# ESP32_Final.net
KiCad netlist of a schematic drawn in EAGLE
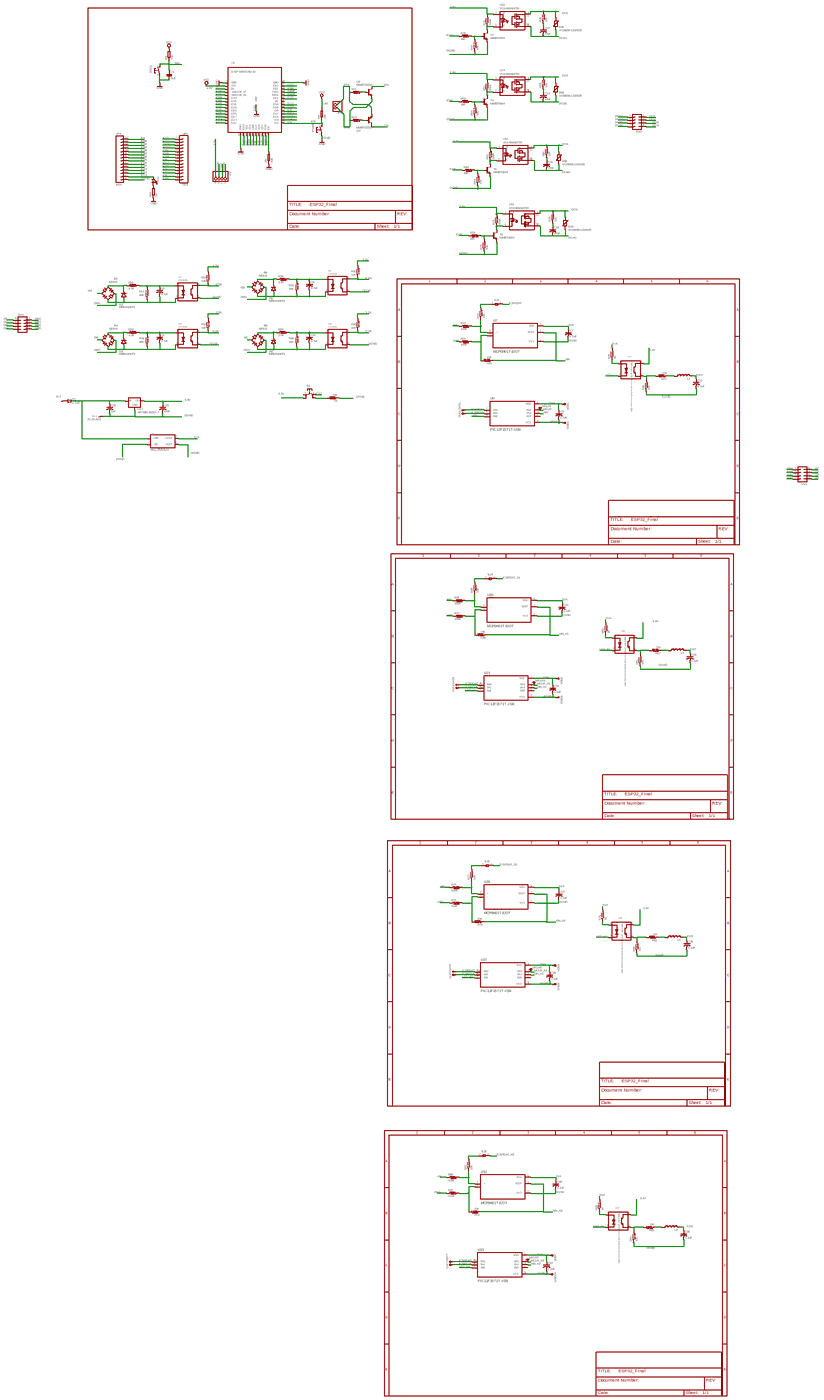
[diagram p0: schematic, sheet 1, overview]
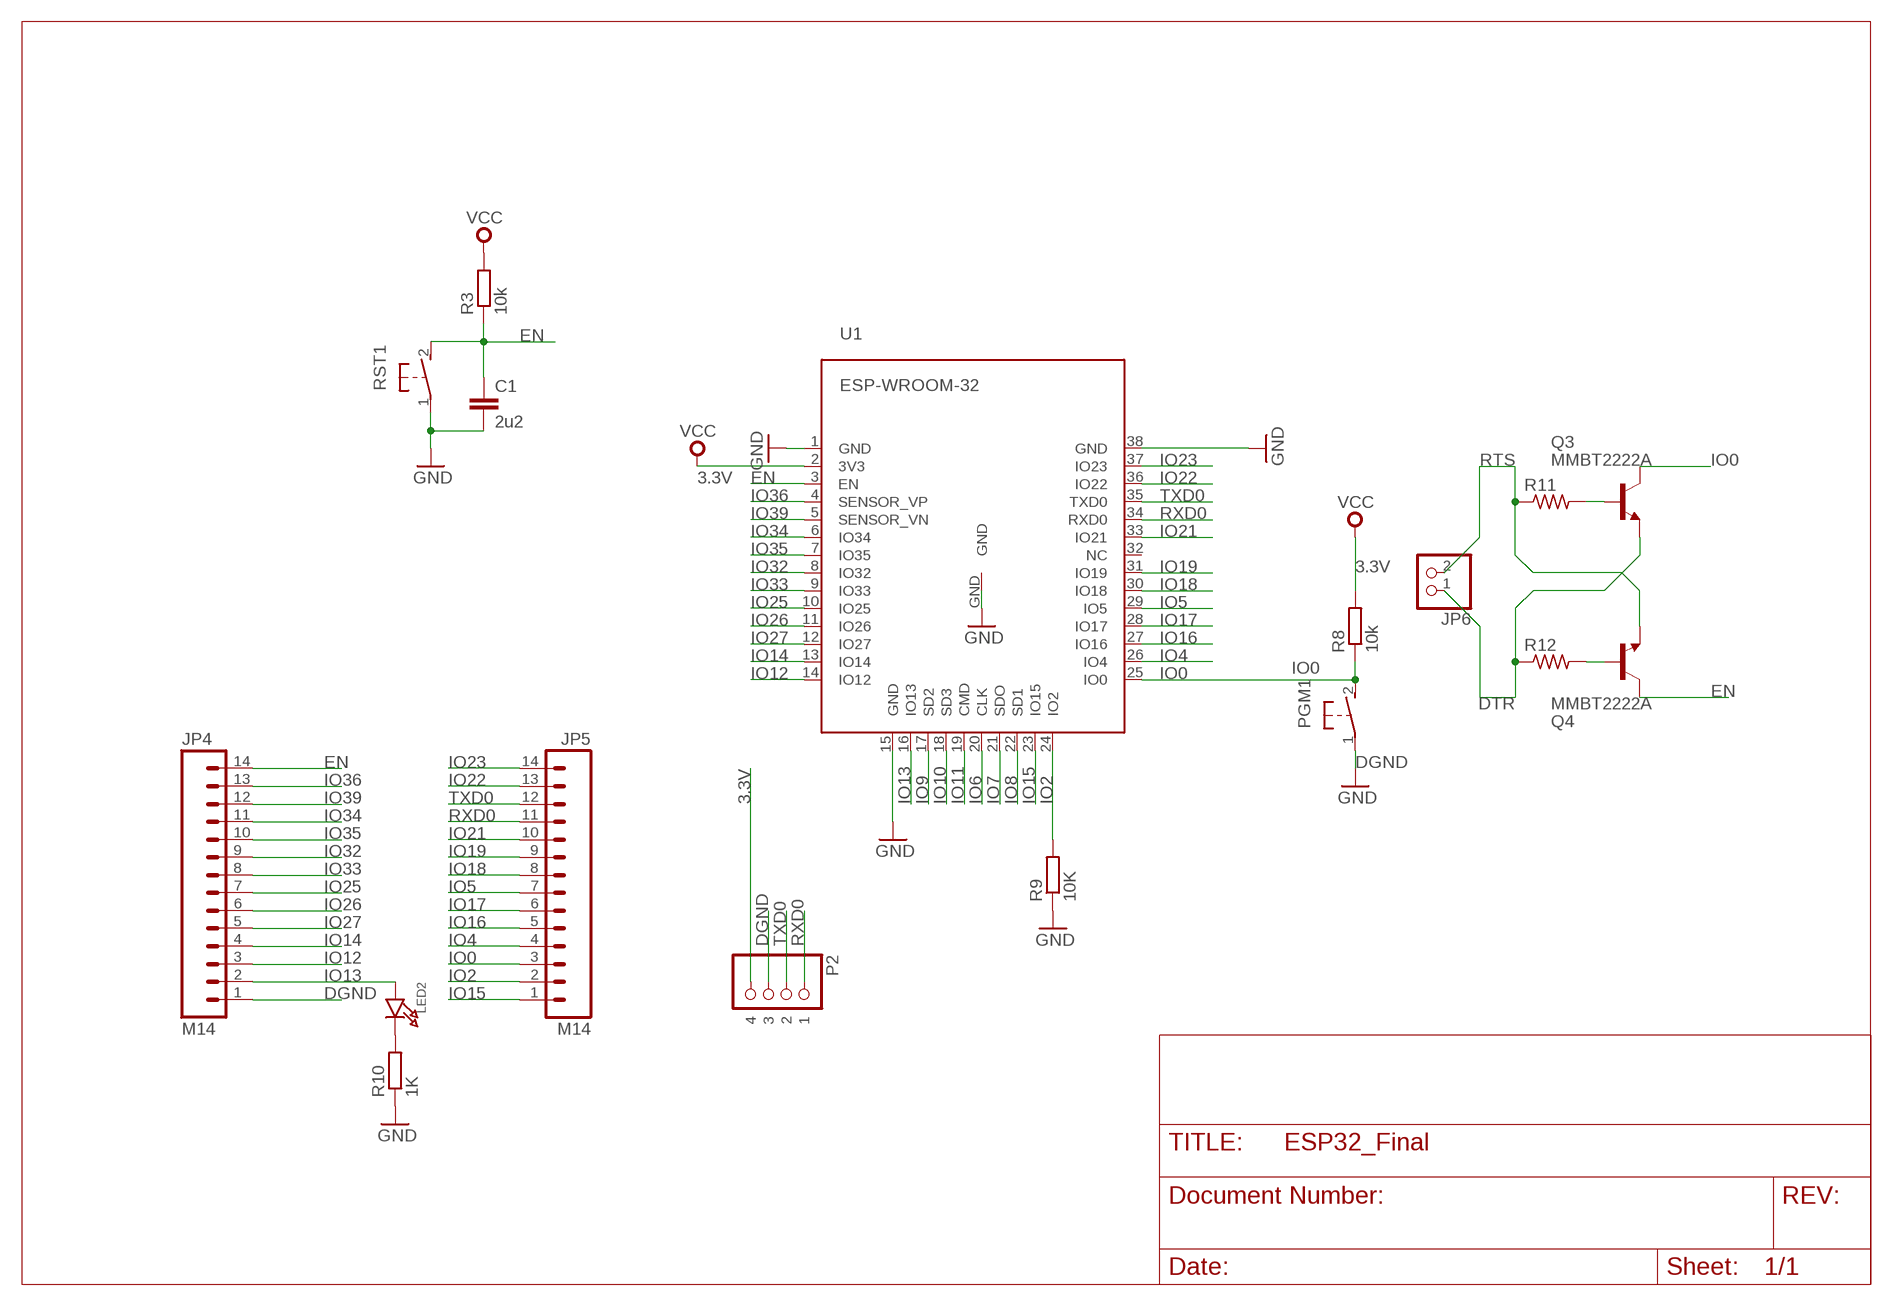
[diagram p1: schematic, sheet 1, part 1 of 5]
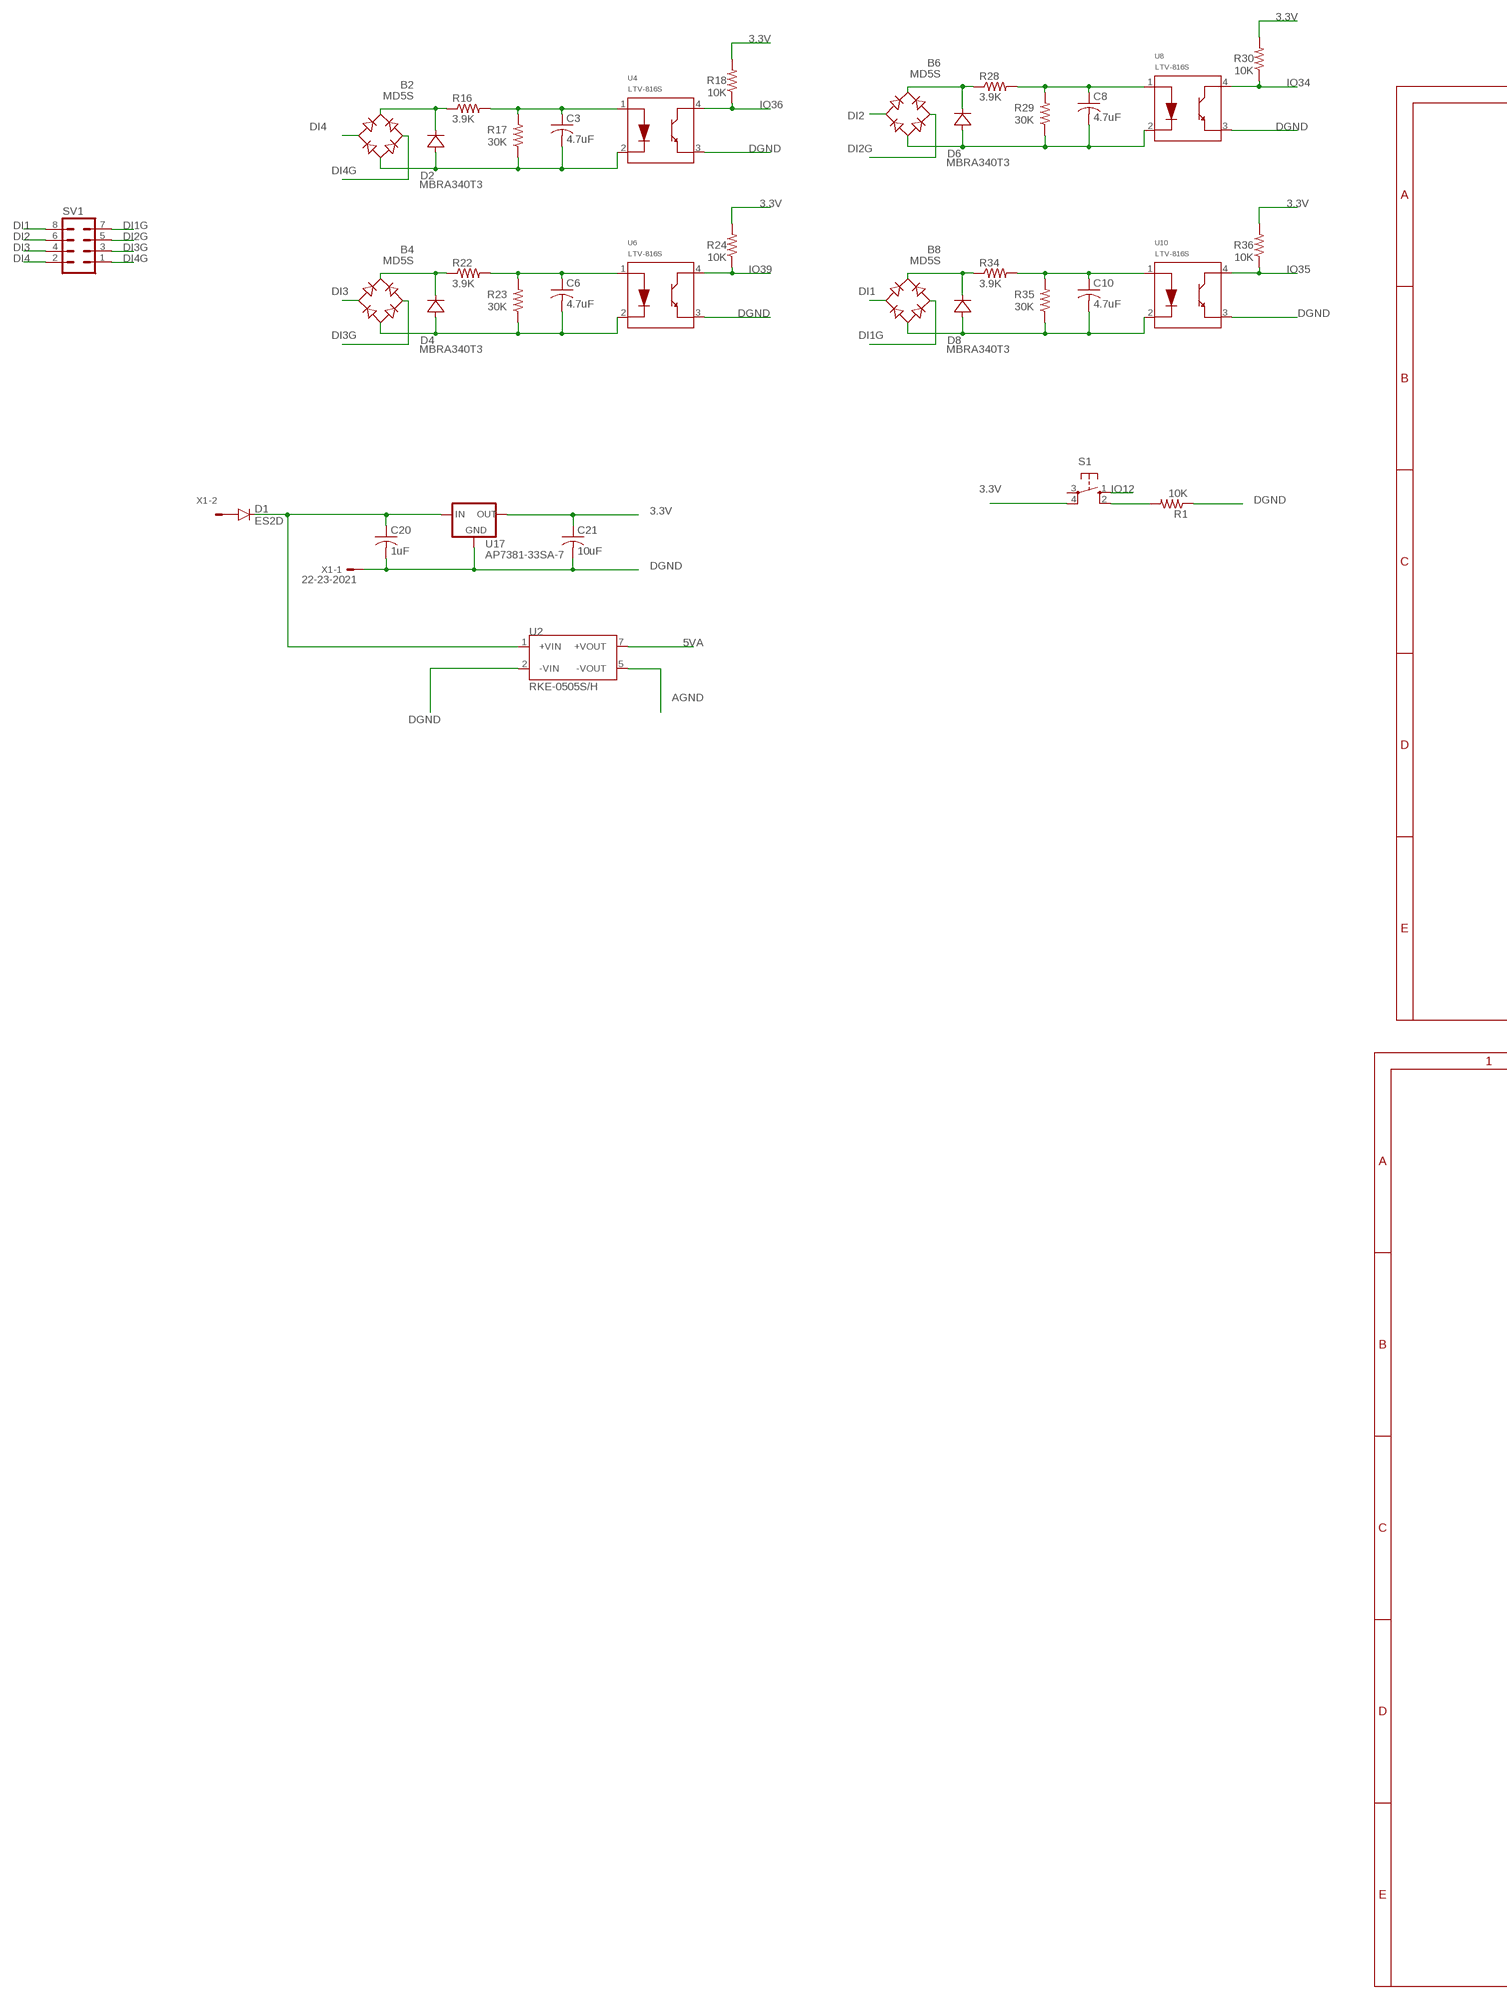
[diagram p2: schematic, sheet 1, part 2 of 5]
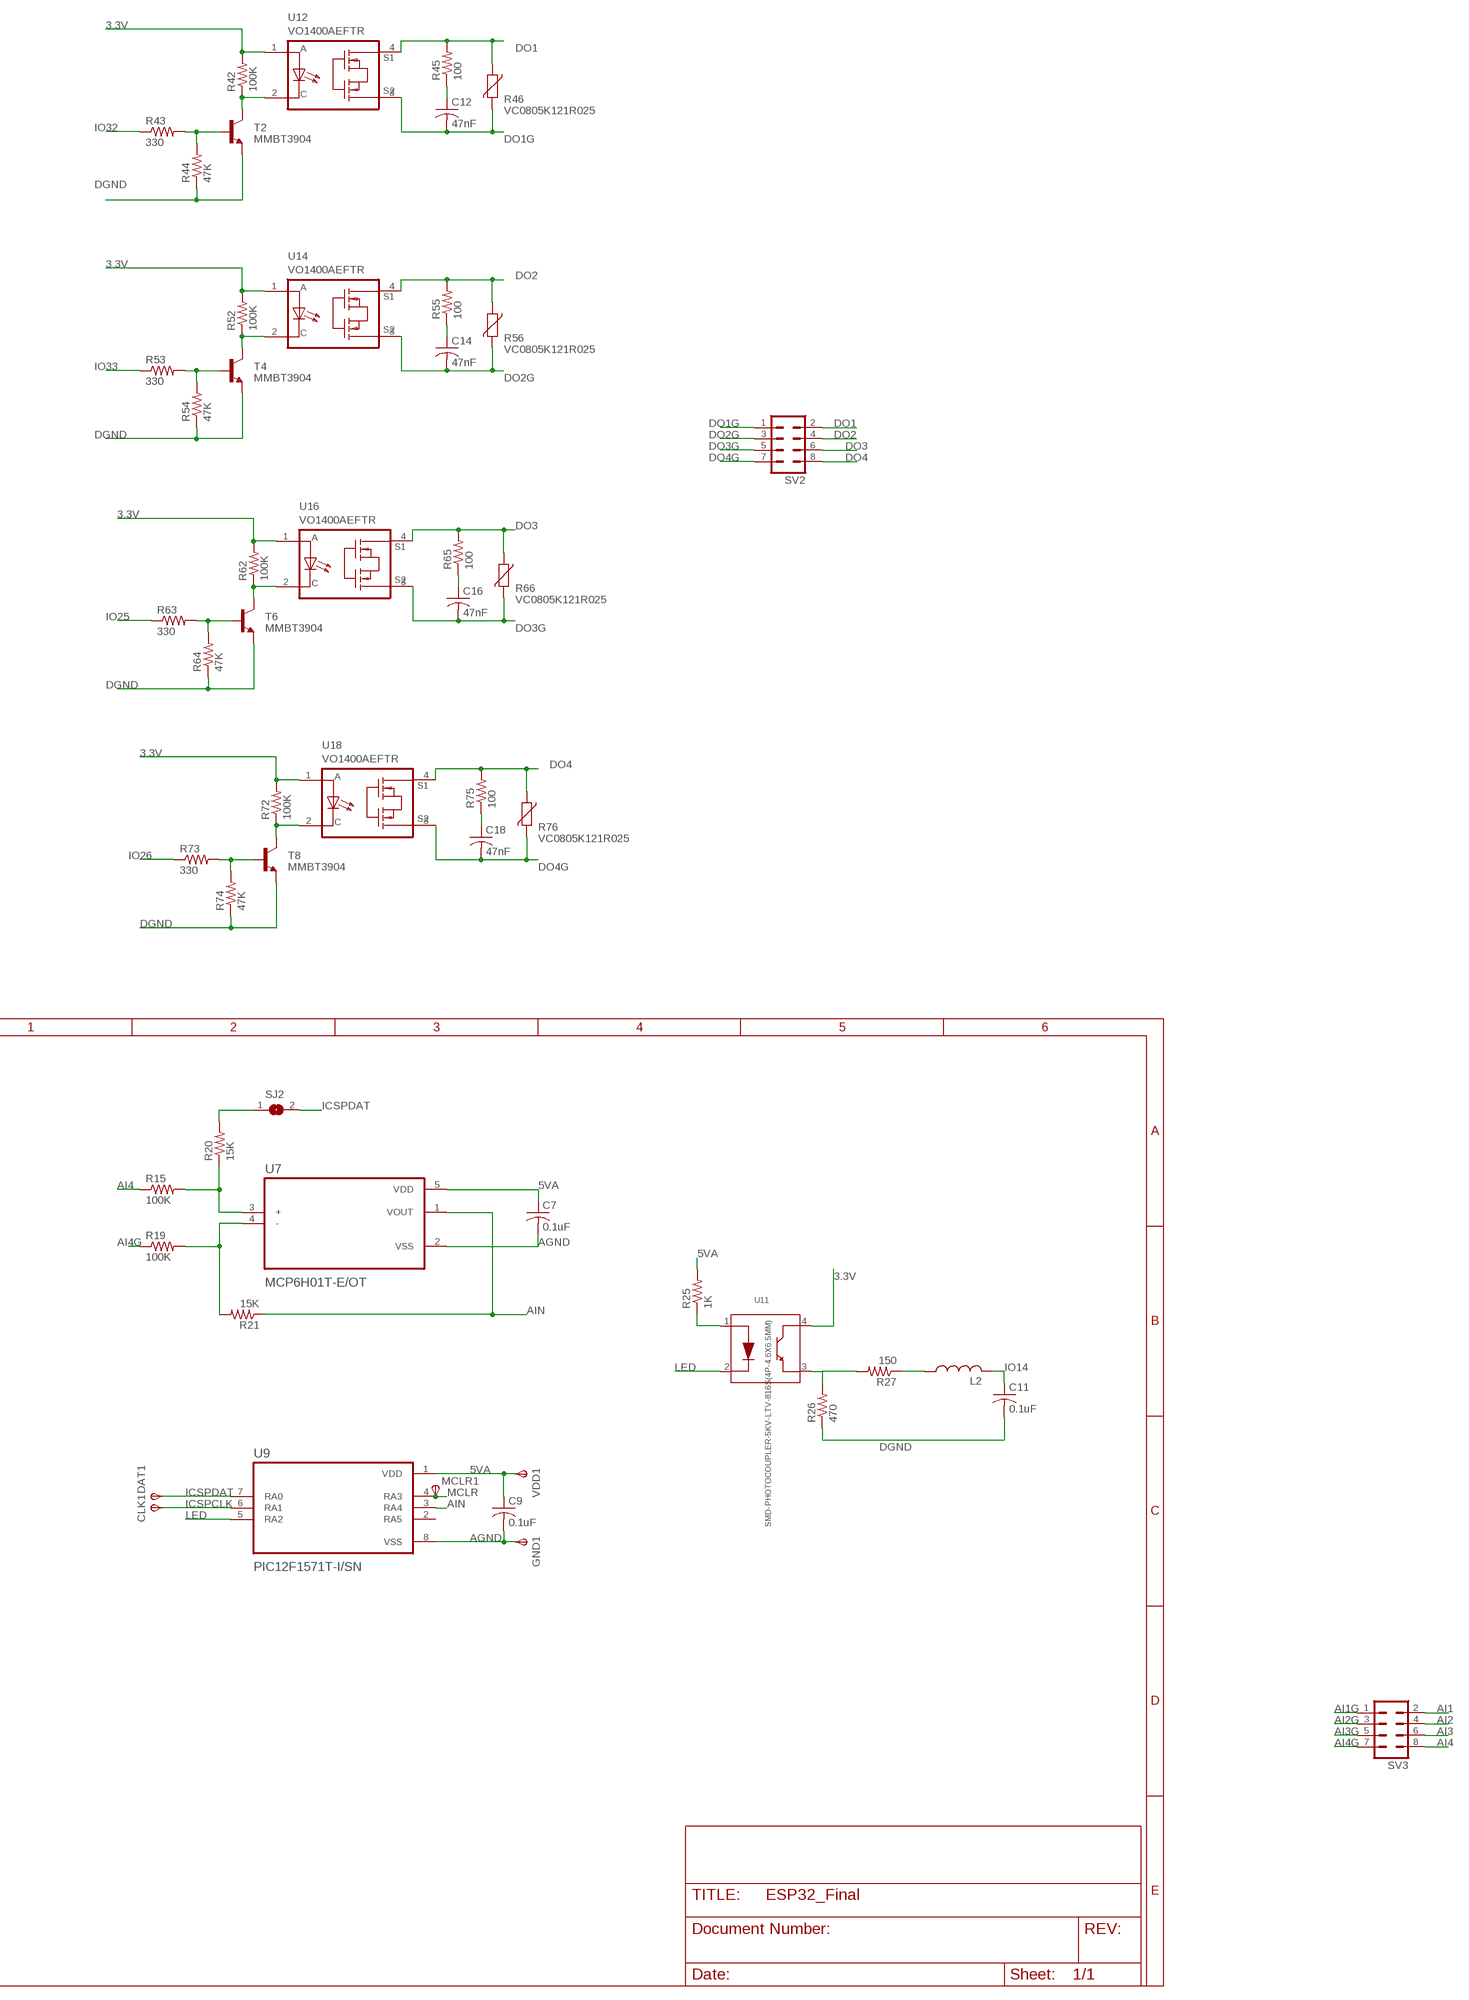
[diagram p3: schematic, sheet 1, part 3 of 5]
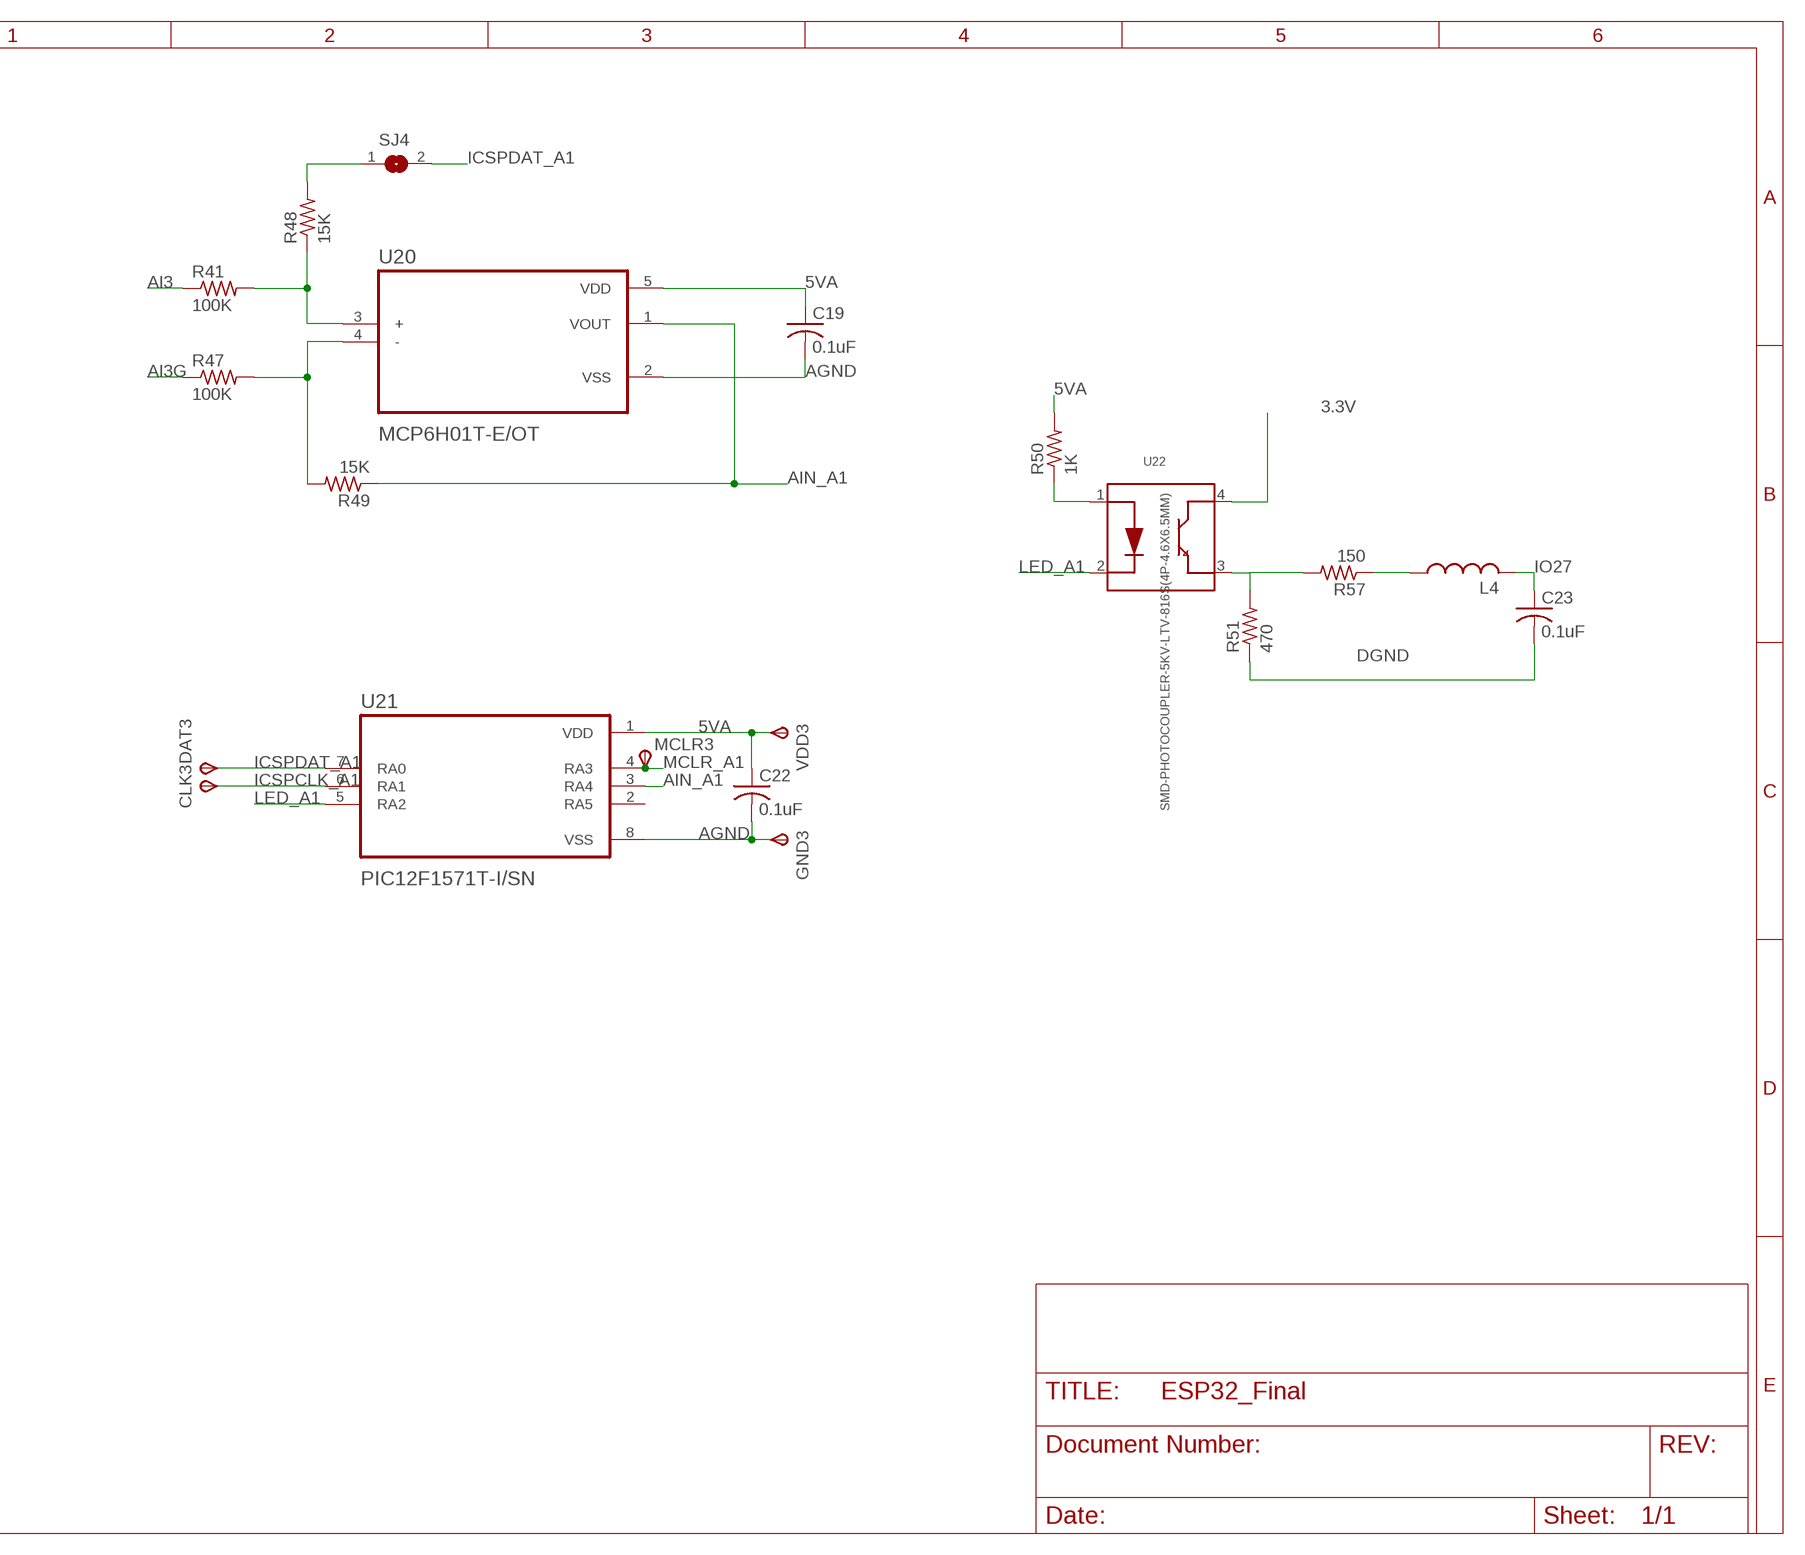
[diagram p4: schematic, sheet 1, part 4 of 5]
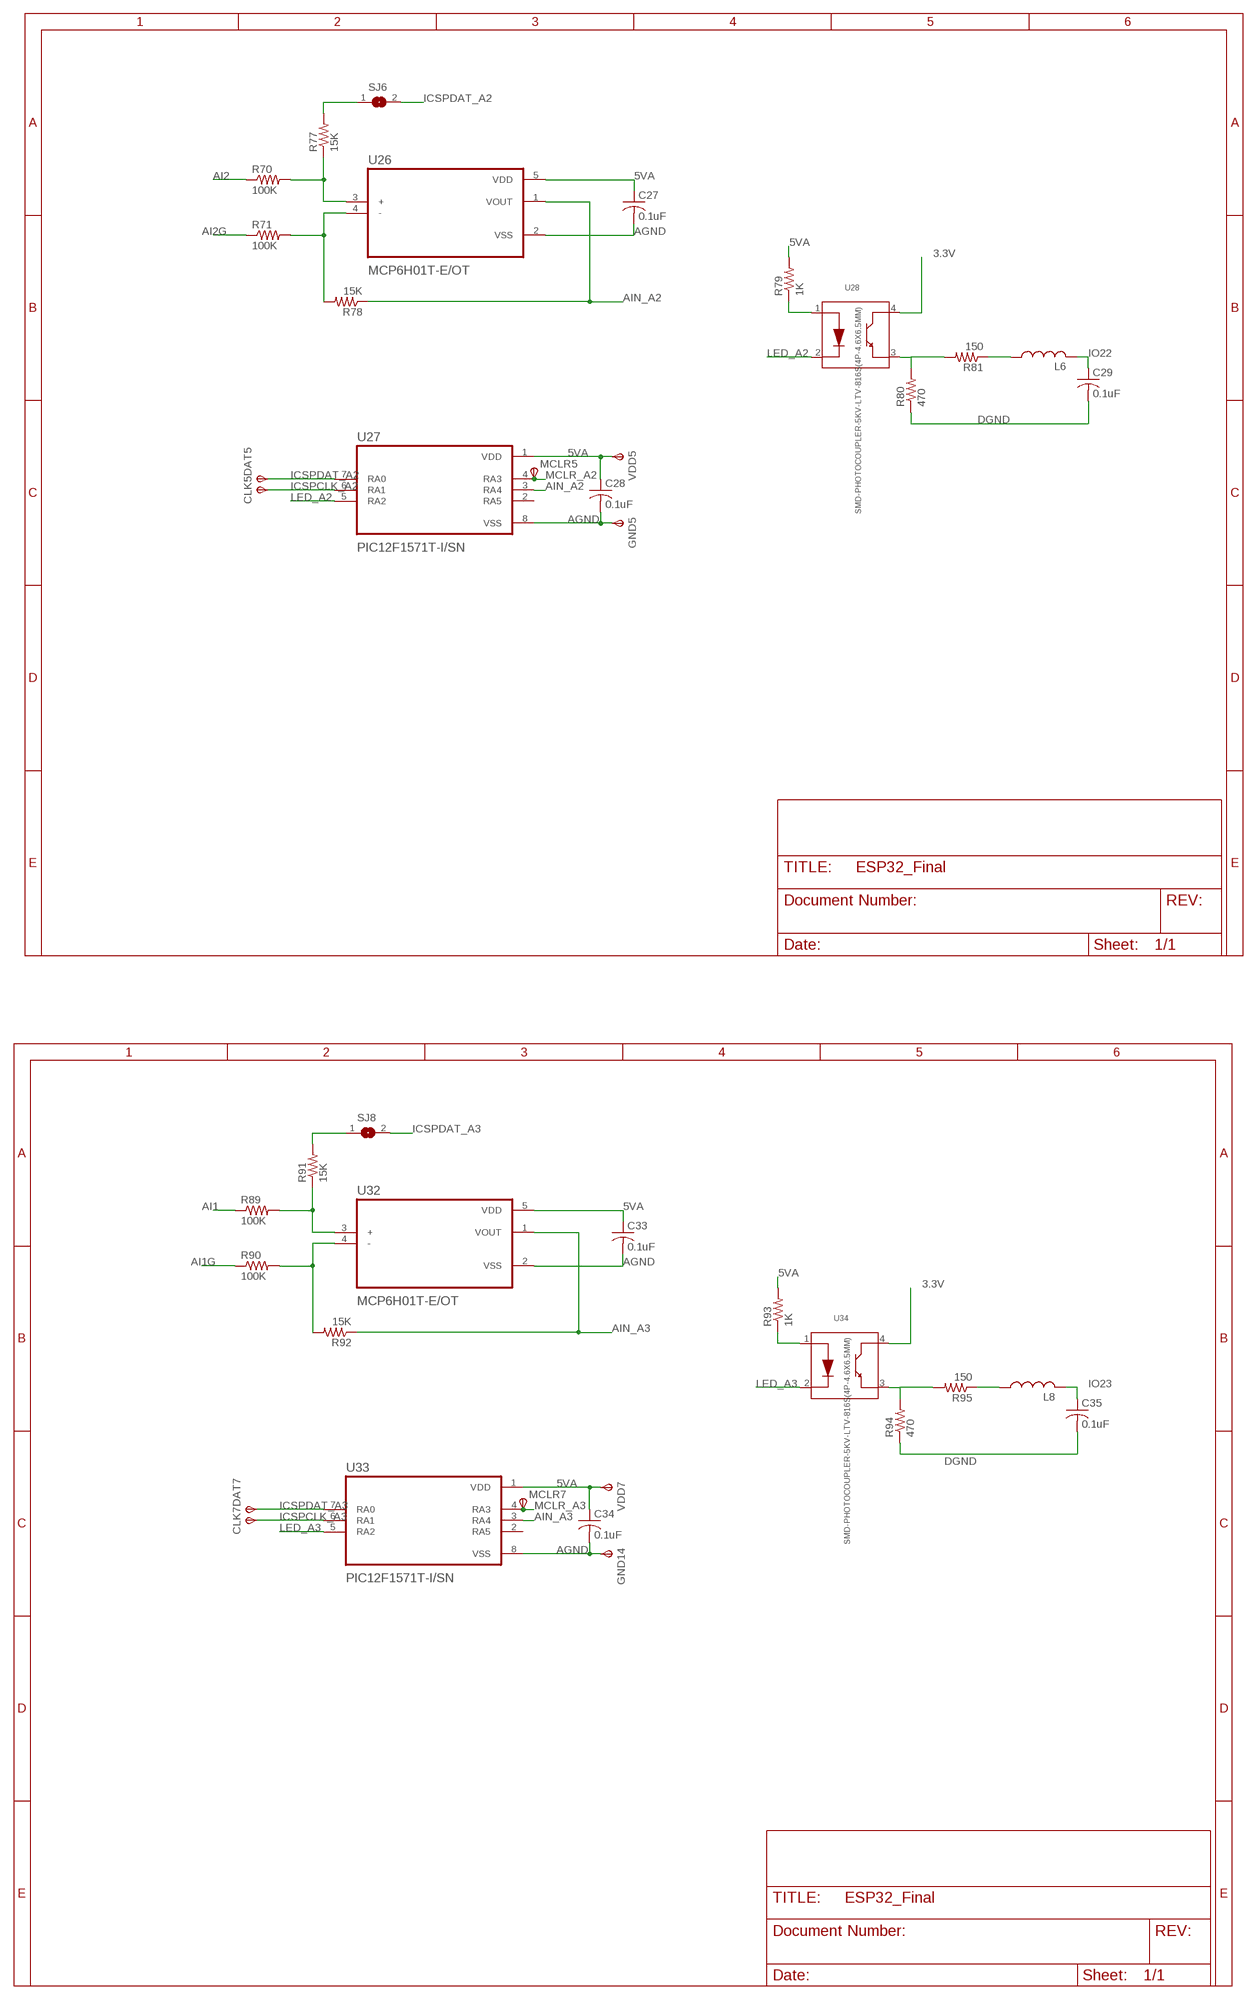
[diagram p5: schematic, sheet 1, part 5 of 5]

(export (version "E")
  (design (tool "Eeschema 10.0.6"))
  (components
    (comp (ref "B2")
      (value "MD5S")
      (footprint "eagle-import:TO-269AA")
      (libsource (lib "eagle-import") (part "RECTIFIER-S80"))
    )
    (comp (ref "B4")
      (value "MD5S")
      (footprint "eagle-import:TO-269AA")
      (libsource (lib "eagle-import") (part "RECTIFIER-S80"))
    )
    (comp (ref "B6")
      (value "MD5S")
      (footprint "eagle-import:TO-269AA")
      (libsource (lib "eagle-import") (part "RECTIFIER-S80"))
    )
    (comp (ref "B8")
      (value "MD5S")
      (footprint "eagle-import:TO-269AA")
      (libsource (lib "eagle-import") (part "RECTIFIER-S80"))
    )
    (comp (ref "C1")
      (value "2u2")
      (footprint "eagle-import:C0603")
      (libsource (lib "eagle-import") (part "C-EUC0603"))
    )
    (comp (ref "C3")
      (value "4.7uF")
      (footprint "eagle-import:C0805")
      (libsource (lib "eagle-import") (part "C-USC0805"))
    )
    (comp (ref "C6")
      (value "4.7uF")
      (footprint "eagle-import:C0805")
      (libsource (lib "eagle-import") (part "C-USC0805"))
    )
    (comp (ref "C7")
      (value "0.1uF")
      (footprint "eagle-import:C0603")
      (libsource (lib "eagle-import") (part "C-USC0603"))
    )
    (comp (ref "C8")
      (value "4.7uF")
      (footprint "eagle-import:C0805")
      (libsource (lib "eagle-import") (part "C-USC0805"))
    )
    (comp (ref "C9")
      (value "0.1uF")
      (footprint "eagle-import:C0603")
      (libsource (lib "eagle-import") (part "C-USC0603"))
    )
    (comp (ref "C10")
      (value "4.7uF")
      (footprint "eagle-import:C0805")
      (libsource (lib "eagle-import") (part "C-USC0805"))
    )
    (comp (ref "C11")
      (value "0.1uF")
      (footprint "eagle-import:C0603")
      (libsource (lib "eagle-import") (part "C-USC0603"))
    )
    (comp (ref "C12")
      (value "47nF")
      (footprint "eagle-import:C0805")
      (libsource (lib "eagle-import") (part "C-USC0805"))
    )
    (comp (ref "C14")
      (value "47nF")
      (footprint "eagle-import:C0805")
      (libsource (lib "eagle-import") (part "C-USC0805"))
    )
    (comp (ref "C16")
      (value "47nF")
      (footprint "eagle-import:C0805")
      (libsource (lib "eagle-import") (part "C-USC0805"))
    )
    (comp (ref "C18")
      (value "47nF")
      (footprint "eagle-import:C0805")
      (libsource (lib "eagle-import") (part "C-USC0805"))
    )
    (comp (ref "C19")
      (value "0.1uF")
      (footprint "eagle-import:C0603")
      (libsource (lib "eagle-import") (part "C-USC0603"))
    )
    (comp (ref "C20")
      (value "1uF")
      (footprint "eagle-import:C0603")
      (libsource (lib "eagle-import") (part "C-USC0603"))
    )
    (comp (ref "C21")
      (value "10uF")
      (footprint "eagle-import:C0603")
      (libsource (lib "eagle-import") (part "C-USC0603"))
    )
    (comp (ref "C22")
      (value "0.1uF")
      (footprint "eagle-import:C0603")
      (libsource (lib "eagle-import") (part "C-USC0603"))
    )
    (comp (ref "C23")
      (value "0.1uF")
      (footprint "eagle-import:C0603")
      (libsource (lib "eagle-import") (part "C-USC0603"))
    )
    (comp (ref "C27")
      (value "0.1uF")
      (footprint "eagle-import:C0603")
      (libsource (lib "eagle-import") (part "C-USC0603"))
    )
    (comp (ref "C28")
      (value "0.1uF")
      (footprint "eagle-import:C0603")
      (libsource (lib "eagle-import") (part "C-USC0603"))
    )
    (comp (ref "C29")
      (value "0.1uF")
      (footprint "eagle-import:C0603")
      (libsource (lib "eagle-import") (part "C-USC0603"))
    )
    (comp (ref "C33")
      (value "0.1uF")
      (footprint "eagle-import:C0603")
      (libsource (lib "eagle-import") (part "C-USC0603"))
    )
    (comp (ref "C34")
      (value "0.1uF")
      (footprint "eagle-import:C0603")
      (libsource (lib "eagle-import") (part "C-USC0603"))
    )
    (comp (ref "C35")
      (value "0.1uF")
      (footprint "eagle-import:C0603")
      (libsource (lib "eagle-import") (part "C-USC0603"))
    )
    (comp (ref "CLK1")
      (value "TPSTP14R")
      (footprint "eagle-import:TP14R")
      (libsource (lib "eagle-import") (part "TPSTP14R"))
    )
    (comp (ref "CLK3")
      (value "TPSTP14R")
      (footprint "eagle-import:TP14R")
      (libsource (lib "eagle-import") (part "TPSTP14R"))
    )
    (comp (ref "CLK5")
      (value "TPSTP14R")
      (footprint "eagle-import:TP14R")
      (libsource (lib "eagle-import") (part "TPSTP14R"))
    )
    (comp (ref "CLK7")
      (value "TPSTP14R")
      (footprint "eagle-import:TP14R")
      (libsource (lib "eagle-import") (part "TPSTP14R"))
    )
    (comp (ref "D1")
      (value "ES2D")
      (footprint "eagle-import:SMB")
      (libsource (lib "eagle-import") (part "ES2D"))
    )
    (comp (ref "D2")
      (value "MBRA340T3")
      (footprint "eagle-import:SMA")
      (libsource (lib "eagle-import") (part "MBRA340T3"))
    )
    (comp (ref "D4")
      (value "MBRA340T3")
      (footprint "eagle-import:SMA")
      (libsource (lib "eagle-import") (part "MBRA340T3"))
    )
    (comp (ref "D6")
      (value "MBRA340T3")
      (footprint "eagle-import:SMA")
      (libsource (lib "eagle-import") (part "MBRA340T3"))
    )
    (comp (ref "D8")
      (value "MBRA340T3")
      (footprint "eagle-import:SMA")
      (libsource (lib "eagle-import") (part "MBRA340T3"))
    )
    (comp (ref "DAT1")
      (value "TPSTP14R")
      (footprint "eagle-import:TP14R")
      (libsource (lib "eagle-import") (part "TPSTP14R"))
    )
    (comp (ref "DAT3")
      (value "TPSTP14R")
      (footprint "eagle-import:TP14R")
      (libsource (lib "eagle-import") (part "TPSTP14R"))
    )
    (comp (ref "DAT5")
      (value "TPSTP14R")
      (footprint "eagle-import:TP14R")
      (libsource (lib "eagle-import") (part "TPSTP14R"))
    )
    (comp (ref "DAT7")
      (value "TPSTP14R")
      (footprint "eagle-import:TP14R")
      (libsource (lib "eagle-import") (part "TPSTP14R"))
    )
    (comp (ref "GND1")
      (value "TPSTP14R")
      (footprint "eagle-import:TP14R")
      (libsource (lib "eagle-import") (part "TPSTP14R"))
    )
    (comp (ref "GND3")
      (value "TPSTP14R")
      (footprint "eagle-import:TP14R")
      (libsource (lib "eagle-import") (part "TPSTP14R"))
    )
    (comp (ref "GND5")
      (value "TPSTP14R")
      (footprint "eagle-import:TP14R")
      (libsource (lib "eagle-import") (part "TPSTP14R"))
    )
    (comp (ref "GND14")
      (value "TPSTP14R")
      (footprint "eagle-import:TP14R")
      (libsource (lib "eagle-import") (part "TPSTP14R"))
    )
    (comp (ref "JP4")
      (value "M14")
      (footprint "eagle-import:1X14")
      (libsource (lib "eagle-import") (part "M14"))
    )
    (comp (ref "JP5")
      (value "M14")
      (footprint "eagle-import:1X14")
      (libsource (lib "eagle-import") (part "M14"))
    )
    (comp (ref "JP6")
      (value "HEADER-1X2ROUND")
      (footprint "eagle-import:1X02_ROUND")
      (libsource (lib "eagle-import") (part "HEADER-1X2ROUND"))
    )
    (comp (ref "L2")
      (value "L-USL2012C")
      (footprint "eagle-import:L2012C")
      (libsource (lib "eagle-import") (part "L-USL2012C"))
    )
    (comp (ref "L4")
      (value "L-USL2012C")
      (footprint "eagle-import:L2012C")
      (libsource (lib "eagle-import") (part "L-USL2012C"))
    )
    (comp (ref "L6")
      (value "L-USL2012C")
      (footprint "eagle-import:L2012C")
      (libsource (lib "eagle-import") (part "L-USL2012C"))
    )
    (comp (ref "L8")
      (value "L-USL2012C")
      (footprint "eagle-import:L2012C")
      (libsource (lib "eagle-import") (part "L-USL2012C"))
    )
    (comp (ref "LED2")
      (value "LED0603")
      (footprint "eagle-import:CHIPLED_0603")
      (libsource (lib "eagle-import") (part "LED0603"))
    )
    (comp (ref "MCLR1")
      (value "TPSTP14R")
      (footprint "eagle-import:TP14R")
      (libsource (lib "eagle-import") (part "TPSTP14R"))
    )
    (comp (ref "MCLR3")
      (value "TPSTP14R")
      (footprint "eagle-import:TP14R")
      (libsource (lib "eagle-import") (part "TPSTP14R"))
    )
    (comp (ref "MCLR5")
      (value "TPSTP14R")
      (footprint "eagle-import:TP14R")
      (libsource (lib "eagle-import") (part "TPSTP14R"))
    )
    (comp (ref "MCLR7")
      (value "TPSTP14R")
      (footprint "eagle-import:TP14R")
      (libsource (lib "eagle-import") (part "TPSTP14R"))
    )
    (comp (ref "P2")
      (value "HEADER-1X4ROUND")
      (footprint "eagle-import:1X04_ROUND")
      (libsource (lib "eagle-import") (part "HEADER-1X4ROUND"))
    )
    (comp (ref "PGM1")
      (value "DTSM-3")
      (footprint "eagle-import:DTSM-3")
      (libsource (lib "eagle-import") (part "DTSM-3"))
    )
    (comp (ref "Q3")
      (value "MMBT2222A")
      (footprint "eagle-import:SOT23")
      (fields (field (name "MF") "STMicroelectronics"))
      (libsource (lib "eagle-import") (part "MMBT2222A"))
    )
    (comp (ref "Q4")
      (value "MMBT2222A")
      (footprint "eagle-import:SOT23")
      (fields (field (name "MF") "STMicroelectronics"))
      (libsource (lib "eagle-import") (part "MMBT2222A"))
    )
    (comp (ref "R1")
      (value "10K")
      (footprint "eagle-import:R0805")
      (libsource (lib "eagle-import") (part "rcl_334_R-US_R0805"))
    )
    (comp (ref "R3")
      (value "10k")
      (footprint "eagle-import:R0603@1")
      (libsource (lib "eagle-import") (part "R-EU_R0603"))
    )
    (comp (ref "R8")
      (value "10k")
      (footprint "eagle-import:R0603@1")
      (libsource (lib "eagle-import") (part "R-EU_R0603"))
    )
    (comp (ref "R9")
      (value "10K")
      (footprint "eagle-import:R0603@1")
      (libsource (lib "eagle-import") (part "R-EU_R0603"))
    )
    (comp (ref "R10")
      (value "1K")
      (footprint "eagle-import:R0603@1")
      (libsource (lib "eagle-import") (part "R-EU_R0603"))
    )
    (comp (ref "R11")
      (value "R-US_R0603")
      (footprint "eagle-import:R0603")
      (libsource (lib "eagle-import") (part "rcl_334_R-US_R0603"))
    )
    (comp (ref "R12")
      (value "R-US_R0603")
      (footprint "eagle-import:R0603")
      (libsource (lib "eagle-import") (part "rcl_334_R-US_R0603"))
    )
    (comp (ref "R15")
      (value "100K")
      (footprint "eagle-import:R0805")
      (libsource (lib "eagle-import") (part "rcl_334_R-US_R0805"))
    )
    (comp (ref "R16")
      (value "3.9K")
      (footprint "eagle-import:R0805")
      (libsource (lib "eagle-import") (part "rcl_334_R-US_R0805"))
    )
    (comp (ref "R17")
      (value "30K")
      (footprint "eagle-import:R0805")
      (libsource (lib "eagle-import") (part "rcl_334_R-US_R0805"))
    )
    (comp (ref "R18")
      (value "10K")
      (footprint "eagle-import:R0603")
      (libsource (lib "eagle-import") (part "R-US_R0603"))
    )
    (comp (ref "R19")
      (value "100K")
      (footprint "eagle-import:R0805")
      (libsource (lib "eagle-import") (part "rcl_334_R-US_R0805"))
    )
    (comp (ref "R20")
      (value "15K")
      (footprint "eagle-import:R0603")
      (libsource (lib "eagle-import") (part "rcl_334_R-US_R0603"))
    )
    (comp (ref "R21")
      (value "15K")
      (footprint "eagle-import:R0603")
      (libsource (lib "eagle-import") (part "rcl_334_R-US_R0603"))
    )
    (comp (ref "R22")
      (value "3.9K")
      (footprint "eagle-import:R0805")
      (libsource (lib "eagle-import") (part "rcl_334_R-US_R0805"))
    )
    (comp (ref "R23")
      (value "30K")
      (footprint "eagle-import:R0805")
      (libsource (lib "eagle-import") (part "rcl_334_R-US_R0805"))
    )
    (comp (ref "R24")
      (value "10K")
      (footprint "eagle-import:R0603")
      (libsource (lib "eagle-import") (part "R-US_R0603"))
    )
    (comp (ref "R25")
      (value "1K")
      (footprint "eagle-import:R0805")
      (libsource (lib "eagle-import") (part "rcl_334_R-US_R0805"))
    )
    (comp (ref "R26")
      (value "470")
      (footprint "eagle-import:R0805")
      (libsource (lib "eagle-import") (part "rcl_334_R-US_R0805"))
    )
    (comp (ref "R27")
      (value "150")
      (footprint "eagle-import:R0805")
      (libsource (lib "eagle-import") (part "rcl_334_R-US_R0805"))
    )
    (comp (ref "R28")
      (value "3.9K")
      (footprint "eagle-import:R0805")
      (libsource (lib "eagle-import") (part "rcl_334_R-US_R0805"))
    )
    (comp (ref "R29")
      (value "30K")
      (footprint "eagle-import:R0805")
      (libsource (lib "eagle-import") (part "rcl_334_R-US_R0805"))
    )
    (comp (ref "R30")
      (value "10K")
      (footprint "eagle-import:R0603")
      (libsource (lib "eagle-import") (part "R-US_R0603"))
    )
    (comp (ref "R34")
      (value "3.9K")
      (footprint "eagle-import:R0805")
      (libsource (lib "eagle-import") (part "rcl_334_R-US_R0805"))
    )
    (comp (ref "R35")
      (value "30K")
      (footprint "eagle-import:R0805")
      (libsource (lib "eagle-import") (part "rcl_334_R-US_R0805"))
    )
    (comp (ref "R36")
      (value "10K")
      (footprint "eagle-import:R0603")
      (libsource (lib "eagle-import") (part "R-US_R0603"))
    )
    (comp (ref "R41")
      (value "100K")
      (footprint "eagle-import:R0805")
      (libsource (lib "eagle-import") (part "rcl_334_R-US_R0805"))
    )
    (comp (ref "R42")
      (value "100K")
      (footprint "eagle-import:R0603")
      (libsource (lib "eagle-import") (part "rcl_334_R-US_R0603"))
    )
    (comp (ref "R43")
      (value "330")
      (footprint "eagle-import:R0603")
      (libsource (lib "eagle-import") (part "rcl_334_R-US_R0603"))
    )
    (comp (ref "R44")
      (value "47K")
      (footprint "eagle-import:R0603")
      (libsource (lib "eagle-import") (part "rcl_334_R-US_R0603"))
    )
    (comp (ref "R45")
      (value "100")
      (footprint "eagle-import:R1210")
      (libsource (lib "eagle-import") (part "rcl_334_R-US_R1210"))
    )
    (comp (ref "R46")
      (value "VC0805K121R025")
      (footprint "eagle-import:CT_CN0805")
      (libsource (lib "eagle-import") (part "VARISTORCN0805"))
    )
    (comp (ref "R47")
      (value "100K")
      (footprint "eagle-import:R0805")
      (libsource (lib "eagle-import") (part "rcl_334_R-US_R0805"))
    )
    (comp (ref "R48")
      (value "15K")
      (footprint "eagle-import:R0603")
      (libsource (lib "eagle-import") (part "rcl_334_R-US_R0603"))
    )
    (comp (ref "R49")
      (value "15K")
      (footprint "eagle-import:R0603")
      (libsource (lib "eagle-import") (part "rcl_334_R-US_R0603"))
    )
    (comp (ref "R50")
      (value "1K")
      (footprint "eagle-import:R0805")
      (libsource (lib "eagle-import") (part "rcl_334_R-US_R0805"))
    )
    (comp (ref "R51")
      (value "470")
      (footprint "eagle-import:R0805")
      (libsource (lib "eagle-import") (part "rcl_334_R-US_R0805"))
    )
    (comp (ref "R52")
      (value "100K")
      (footprint "eagle-import:R0603")
      (libsource (lib "eagle-import") (part "rcl_334_R-US_R0603"))
    )
    (comp (ref "R53")
      (value "330")
      (footprint "eagle-import:R0603")
      (libsource (lib "eagle-import") (part "rcl_334_R-US_R0603"))
    )
    (comp (ref "R54")
      (value "47K")
      (footprint "eagle-import:R0603")
      (libsource (lib "eagle-import") (part "rcl_334_R-US_R0603"))
    )
    (comp (ref "R55")
      (value "100")
      (footprint "eagle-import:R1210")
      (libsource (lib "eagle-import") (part "rcl_334_R-US_R1210"))
    )
    (comp (ref "R56")
      (value "VC0805K121R025")
      (footprint "eagle-import:CT_CN0805")
      (libsource (lib "eagle-import") (part "VARISTORCN0805"))
    )
    (comp (ref "R57")
      (value "150")
      (footprint "eagle-import:R0805")
      (libsource (lib "eagle-import") (part "rcl_334_R-US_R0805"))
    )
    (comp (ref "R62")
      (value "100K")
      (footprint "eagle-import:R0603")
      (libsource (lib "eagle-import") (part "rcl_334_R-US_R0603"))
    )
    (comp (ref "R63")
      (value "330")
      (footprint "eagle-import:R0603")
      (libsource (lib "eagle-import") (part "rcl_334_R-US_R0603"))
    )
    (comp (ref "R64")
      (value "47K")
      (footprint "eagle-import:R0603")
      (libsource (lib "eagle-import") (part "rcl_334_R-US_R0603"))
    )
    (comp (ref "R65")
      (value "100")
      (footprint "eagle-import:R1210")
      (libsource (lib "eagle-import") (part "rcl_334_R-US_R1210"))
    )
    (comp (ref "R66")
      (value "VC0805K121R025")
      (footprint "eagle-import:CT_CN0805")
      (libsource (lib "eagle-import") (part "VARISTORCN0805"))
    )
    (comp (ref "R70")
      (value "100K")
      (footprint "eagle-import:R0805")
      (libsource (lib "eagle-import") (part "rcl_334_R-US_R0805"))
    )
    (comp (ref "R71")
      (value "100K")
      (footprint "eagle-import:R0805")
      (libsource (lib "eagle-import") (part "rcl_334_R-US_R0805"))
    )
    (comp (ref "R72")
      (value "100K")
      (footprint "eagle-import:R0603")
      (libsource (lib "eagle-import") (part "rcl_334_R-US_R0603"))
    )
    (comp (ref "R73")
      (value "330")
      (footprint "eagle-import:R0603")
      (libsource (lib "eagle-import") (part "rcl_334_R-US_R0603"))
    )
    (comp (ref "R74")
      (value "47K")
      (footprint "eagle-import:R0603")
      (libsource (lib "eagle-import") (part "rcl_334_R-US_R0603"))
    )
    (comp (ref "R75")
      (value "100")
      (footprint "eagle-import:R1210")
      (libsource (lib "eagle-import") (part "rcl_334_R-US_R1210"))
    )
    (comp (ref "R76")
      (value "VC0805K121R025")
      (footprint "eagle-import:CT_CN0805")
      (libsource (lib "eagle-import") (part "VARISTORCN0805"))
    )
    (comp (ref "R77")
      (value "15K")
      (footprint "eagle-import:R0603")
      (libsource (lib "eagle-import") (part "rcl_334_R-US_R0603"))
    )
    (comp (ref "R78")
      (value "15K")
      (footprint "eagle-import:R0603")
      (libsource (lib "eagle-import") (part "rcl_334_R-US_R0603"))
    )
    (comp (ref "R79")
      (value "1K")
      (footprint "eagle-import:R0805")
      (libsource (lib "eagle-import") (part "rcl_334_R-US_R0805"))
    )
    (comp (ref "R80")
      (value "470")
      (footprint "eagle-import:R0805")
      (libsource (lib "eagle-import") (part "rcl_334_R-US_R0805"))
    )
    (comp (ref "R81")
      (value "150")
      (footprint "eagle-import:R0805")
      (libsource (lib "eagle-import") (part "rcl_334_R-US_R0805"))
    )
    (comp (ref "R89")
      (value "100K")
      (footprint "eagle-import:R0805")
      (libsource (lib "eagle-import") (part "rcl_334_R-US_R0805"))
    )
    (comp (ref "R90")
      (value "100K")
      (footprint "eagle-import:R0805")
      (libsource (lib "eagle-import") (part "rcl_334_R-US_R0805"))
    )
    (comp (ref "R91")
      (value "15K")
      (footprint "eagle-import:R0603")
      (libsource (lib "eagle-import") (part "rcl_334_R-US_R0603"))
    )
    (comp (ref "R92")
      (value "15K")
      (footprint "eagle-import:R0603")
      (libsource (lib "eagle-import") (part "rcl_334_R-US_R0603"))
    )
    (comp (ref "R93")
      (value "1K")
      (footprint "eagle-import:R0805")
      (libsource (lib "eagle-import") (part "rcl_334_R-US_R0805"))
    )
    (comp (ref "R94")
      (value "470")
      (footprint "eagle-import:R0805")
      (libsource (lib "eagle-import") (part "rcl_334_R-US_R0805"))
    )
    (comp (ref "R95")
      (value "150")
      (footprint "eagle-import:R0805")
      (libsource (lib "eagle-import") (part "rcl_334_R-US_R0805"))
    )
    (comp (ref "RST1")
      (value "DTSM-3")
      (footprint "eagle-import:DTSM-3")
      (libsource (lib "eagle-import") (part "DTSM-3"))
    )
    (comp (ref "S1")
      (value "10-XX")
      (footprint "eagle-import:B3F-10XX")
      (fields (field (name "MPN") "B3F-1000"))
      (libsource (lib "eagle-import") (part "10-XX"))
    )
    (comp (ref "SJ2") (value "SJ") (footprint "eagle-import:SJ") (libsource (lib "eagle-import") (part "SJ")))
    (comp (ref "SJ4") (value "SJ") (footprint "eagle-import:SJ") (libsource (lib "eagle-import") (part "SJ")))
    (comp (ref "SJ6") (value "SJ") (footprint "eagle-import:SJ") (libsource (lib "eagle-import") (part "SJ")))
    (comp (ref "SJ8") (value "SJ") (footprint "eagle-import:SJ") (libsource (lib "eagle-import") (part "SJ")))
    (comp (ref "SV1")
      (value "MA04-2")
      (footprint "eagle-import:MA04-2")
      (libsource (lib "eagle-import") (part "MA04-2"))
    )
    (comp (ref "SV2")
      (value "MA04-2")
      (footprint "eagle-import:MA04-2")
      (libsource (lib "eagle-import") (part "MA04-2"))
    )
    (comp (ref "SV3")
      (value "MA04-2")
      (footprint "eagle-import:MA04-2")
      (libsource (lib "eagle-import") (part "MA04-2"))
    )
    (comp (ref "T2")
      (value "MMBT3904")
      (footprint "eagle-import:SOT23-BEC")
      (libsource (lib "eagle-import") (part "-NPN-SOT23-BECMMBT3904LT1"))
    )
    (comp (ref "T4")
      (value "MMBT3904")
      (footprint "eagle-import:SOT23-BEC")
      (libsource (lib "eagle-import") (part "-NPN-SOT23-BECMMBT3904LT1"))
    )
    (comp (ref "T6")
      (value "MMBT3904")
      (footprint "eagle-import:SOT23-BEC")
      (libsource (lib "eagle-import") (part "-NPN-SOT23-BECMMBT3904LT1"))
    )
    (comp (ref "T8")
      (value "MMBT3904")
      (footprint "eagle-import:SOT23-BEC")
      (libsource (lib "eagle-import") (part "-NPN-SOT23-BECMMBT3904LT1"))
    )
    (comp (ref "U1")
      (value "ESP-WROOM-32")
      (footprint "eagle-import:ESP-WROOM-32")
      (libsource (lib "eagle-import") (part "ESP-WROOM-32"))
    )
    (comp (ref "U2")
      (value "RKE-0505S/H")
      (footprint "eagle-import:CONV_RKE-0505S_H")
      (fields (field (name "MF") "Recom Power"))
      (libsource (lib "eagle-import") (part "RKE-0505S/H"))
    )
    (comp (ref "U4")
      (value "LTV-816S")
      (footprint "eagle-import:SMD4-2.54-4.6X6.5MM")
      (fields (field (name "MF") "Lite-On Inc."))
      (libsource (lib "eagle-import") (part "SMD-PHOTOCOUPLER-5KV-LTV-816S(4P-4.6X6.5MM)"))
    )
    (comp (ref "U6")
      (value "LTV-816S")
      (footprint "eagle-import:SMD4-2.54-4.6X6.5MM")
      (fields (field (name "MF") "Lite-On Inc."))
      (libsource (lib "eagle-import") (part "SMD-PHOTOCOUPLER-5KV-LTV-816S(4P-4.6X6.5MM)"))
    )
    (comp (ref "U7")
      (value "MCP6H01T-E/OT")
      (footprint "eagle-import:SOT95P280X145-5N")
      (fields (field (name "MF") "Microchip"))
      (libsource (lib "eagle-import") (part "MCP6H01T-E/OT"))
    )
    (comp (ref "U8")
      (value "LTV-816S")
      (footprint "eagle-import:SMD4-2.54-4.6X6.5MM")
      (fields (field (name "MF") "Lite-On Inc."))
      (libsource (lib "eagle-import") (part "SMD-PHOTOCOUPLER-5KV-LTV-816S(4P-4.6X6.5MM)"))
    )
    (comp (ref "U9")
      (value "PIC12F1571T-I/SN")
      (footprint "eagle-import:SOIC127P600X175-8N")
      (fields (field (name "MF") "Microchip"))
      (libsource (lib "eagle-import") (part "PIC12F1571T-I/SN"))
    )
    (comp (ref "U10")
      (value "LTV-816S")
      (footprint "eagle-import:SMD4-2.54-4.6X6.5MM")
      (fields (field (name "MF") "Lite-On Inc."))
      (libsource (lib "eagle-import") (part "SMD-PHOTOCOUPLER-5KV-LTV-816S(4P-4.6X6.5MM)"))
    )
    (comp (ref "U11")
      (value "SMD-PHOTOCOUPLER-5KV-LTV-816S(4P-4.6X6.5MM)")
      (footprint "eagle-import:SMD4-2.54-4.6X6.5MM")
      (fields (field (name "MF") "Lite-On Inc.") (field (name "MP") "LTV-816S"))
      (libsource (lib "eagle-import") (part "SMD-PHOTOCOUPLER-5KV-LTV-816S(4P-4.6X6.5MM)"))
    )
    (comp (ref "U12")
      (value "VO1400AEFTR")
      (footprint "eagle-import:SOIC254P695X242-4N")
      (fields (field (name "MF") "Vishay"))
      (libsource (lib "eagle-import") (part "VO1400AEFTR"))
    )
    (comp (ref "U14")
      (value "VO1400AEFTR")
      (footprint "eagle-import:SOIC254P695X242-4N")
      (fields (field (name "MF") "Vishay"))
      (libsource (lib "eagle-import") (part "VO1400AEFTR"))
    )
    (comp (ref "U16")
      (value "VO1400AEFTR")
      (footprint "eagle-import:SOIC254P695X242-4N")
      (fields (field (name "MF") "Vishay"))
      (libsource (lib "eagle-import") (part "VO1400AEFTR"))
    )
    (comp (ref "U17")
      (value "AP7381-33SA-7")
      (footprint "eagle-import:SOT23")
      (libsource (lib "eagle-import") (part "AP7381-33SA-7"))
    )
    (comp (ref "U18")
      (value "VO1400AEFTR")
      (footprint "eagle-import:SOIC254P695X242-4N")
      (fields (field (name "MF") "Vishay"))
      (libsource (lib "eagle-import") (part "VO1400AEFTR"))
    )
    (comp (ref "U20")
      (value "MCP6H01T-E/OT")
      (footprint "eagle-import:SOT95P280X145-5N")
      (fields (field (name "MF") "Microchip"))
      (libsource (lib "eagle-import") (part "MCP6H01T-E/OT"))
    )
    (comp (ref "U21")
      (value "PIC12F1571T-I/SN")
      (footprint "eagle-import:SOIC127P600X175-8N")
      (fields (field (name "MF") "Microchip"))
      (libsource (lib "eagle-import") (part "PIC12F1571T-I/SN"))
    )
    (comp (ref "U22")
      (value "SMD-PHOTOCOUPLER-5KV-LTV-816S(4P-4.6X6.5MM)")
      (footprint "eagle-import:SMD4-2.54-4.6X6.5MM")
      (fields (field (name "MF") "Lite-On Inc.") (field (name "MP") "LTV-816S"))
      (libsource (lib "eagle-import") (part "SMD-PHOTOCOUPLER-5KV-LTV-816S(4P-4.6X6.5MM)"))
    )
    (comp (ref "U26")
      (value "MCP6H01T-E/OT")
      (footprint "eagle-import:SOT95P280X145-5N")
      (fields (field (name "MF") "Microchip"))
      (libsource (lib "eagle-import") (part "MCP6H01T-E/OT"))
    )
    (comp (ref "U27")
      (value "PIC12F1571T-I/SN")
      (footprint "eagle-import:SOIC127P600X175-8N")
      (fields (field (name "MF") "Microchip"))
      (libsource (lib "eagle-import") (part "PIC12F1571T-I/SN"))
    )
    (comp (ref "U28")
      (value "SMD-PHOTOCOUPLER-5KV-LTV-816S(4P-4.6X6.5MM)")
      (footprint "eagle-import:SMD4-2.54-4.6X6.5MM")
      (fields (field (name "MF") "Lite-On Inc.") (field (name "MP") "LTV-816S"))
      (libsource (lib "eagle-import") (part "SMD-PHOTOCOUPLER-5KV-LTV-816S(4P-4.6X6.5MM)"))
    )
    (comp (ref "U32")
      (value "MCP6H01T-E/OT")
      (footprint "eagle-import:SOT95P280X145-5N")
      (fields (field (name "MF") "Microchip"))
      (libsource (lib "eagle-import") (part "MCP6H01T-E/OT"))
    )
    (comp (ref "U33")
      (value "PIC12F1571T-I/SN")
      (footprint "eagle-import:SOIC127P600X175-8N")
      (fields (field (name "MF") "Microchip"))
      (libsource (lib "eagle-import") (part "PIC12F1571T-I/SN"))
    )
    (comp (ref "U34")
      (value "SMD-PHOTOCOUPLER-5KV-LTV-816S(4P-4.6X6.5MM)")
      (footprint "eagle-import:SMD4-2.54-4.6X6.5MM")
      (fields (field (name "MF") "Lite-On Inc.") (field (name "MP") "LTV-816S"))
      (libsource (lib "eagle-import") (part "SMD-PHOTOCOUPLER-5KV-LTV-816S(4P-4.6X6.5MM)"))
    )
    (comp (ref "VDD1")
      (value "TPSTP14R")
      (footprint "eagle-import:TP14R")
      (libsource (lib "eagle-import") (part "TPSTP14R"))
    )
    (comp (ref "VDD3")
      (value "TPSTP14R")
      (footprint "eagle-import:TP14R")
      (libsource (lib "eagle-import") (part "TPSTP14R"))
    )
    (comp (ref "VDD5")
      (value "TPSTP14R")
      (footprint "eagle-import:TP14R")
      (libsource (lib "eagle-import") (part "TPSTP14R"))
    )
    (comp (ref "VDD7")
      (value "TPSTP14R")
      (footprint "eagle-import:TP14R")
      (libsource (lib "eagle-import") (part "TPSTP14R"))
    )
    (comp (ref "X1")
      (value "22-23-2021")
      (footprint "eagle-import:22-23-2021")
      (fields (field (name "MF") "MOLEX"))
      (libsource (lib "eagle-import") (part "22-23-2021"))
    )
  )
  (nets
    (net (code "1") (name "/5VA") (class "Default")
      (node (ref "C19") (pin "1") (pinfunction "1_1") (pintype "passive"))
      (node (ref "C22") (pin "1") (pinfunction "1_1") (pintype "passive"))
      (node (ref "C27") (pin "1") (pinfunction "1_1") (pintype "passive"))
      (node (ref "C28") (pin "1") (pinfunction "1_1") (pintype "passive"))
      (node (ref "C33") (pin "1") (pinfunction "1_1") (pintype "passive"))
      (node (ref "C34") (pin "1") (pinfunction "1_1") (pintype "passive"))
      (node (ref "C7") (pin "1") (pinfunction "1_1") (pintype "passive"))
      (node (ref "C9") (pin "1") (pinfunction "1_1") (pintype "passive"))
      (node (ref "R25") (pin "2") (pinfunction "2_2") (pintype "passive"))
      (node (ref "R50") (pin "2") (pinfunction "2_2") (pintype "passive"))
      (node (ref "R79") (pin "2") (pinfunction "2_2") (pintype "passive"))
      (node (ref "R93") (pin "2") (pinfunction "2_2") (pintype "passive"))
      (node (ref "U2") (pin "7") (pinfunction "+VOUT_7") (pintype "output"))
      (node (ref "U20") (pin "5") (pinfunction "VDD_5") (pintype "power_in"))
      (node (ref "U21") (pin "1") (pinfunction "VDD_1") (pintype "power_in"))
      (node (ref "U26") (pin "5") (pinfunction "VDD_5") (pintype "power_in"))
      (node (ref "U27") (pin "1") (pinfunction "VDD_1") (pintype "power_in"))
      (node (ref "U32") (pin "5") (pinfunction "VDD_5") (pintype "power_in"))
      (node (ref "U33") (pin "1") (pinfunction "VDD_1") (pintype "power_in"))
      (node (ref "U7") (pin "5") (pinfunction "VDD_5") (pintype "power_in"))
      (node (ref "U9") (pin "1") (pinfunction "VDD_1") (pintype "power_in"))
      (node (ref "VDD1") (pin "TP") (pinfunction "PP_TP") (pintype "input"))
      (node (ref "VDD3") (pin "TP") (pinfunction "PP_TP") (pintype "input"))
      (node (ref "VDD5") (pin "TP") (pinfunction "PP_TP") (pintype "input"))
      (node (ref "VDD7") (pin "TP") (pinfunction "PP_TP") (pintype "input"))
    )
    (net (code "2") (name "/AGND") (class "Default")
      (node (ref "C19") (pin "2") (pinfunction "2_2") (pintype "passive"))
      (node (ref "C22") (pin "2") (pinfunction "2_2") (pintype "passive"))
      (node (ref "C27") (pin "2") (pinfunction "2_2") (pintype "passive"))
      (node (ref "C28") (pin "2") (pinfunction "2_2") (pintype "passive"))
      (node (ref "C33") (pin "2") (pinfunction "2_2") (pintype "passive"))
      (node (ref "C34") (pin "2") (pinfunction "2_2") (pintype "passive"))
      (node (ref "C7") (pin "2") (pinfunction "2_2") (pintype "passive"))
      (node (ref "C9") (pin "2") (pinfunction "2_2") (pintype "passive"))
      (node (ref "GND1") (pin "TP") (pinfunction "PP_TP") (pintype "input"))
      (node (ref "GND14") (pin "TP") (pinfunction "PP_TP") (pintype "input"))
      (node (ref "GND3") (pin "TP") (pinfunction "PP_TP") (pintype "input"))
      (node (ref "GND5") (pin "TP") (pinfunction "PP_TP") (pintype "input"))
      (node (ref "U2") (pin "5") (pinfunction "-VOUT_5") (pintype "output"))
      (node (ref "U20") (pin "2") (pinfunction "VSS_2") (pintype "power_in"))
      (node (ref "U21") (pin "8") (pinfunction "VSS_8") (pintype "power_in"))
      (node (ref "U26") (pin "2") (pinfunction "VSS_2") (pintype "power_in"))
      (node (ref "U27") (pin "8") (pinfunction "VSS_8") (pintype "power_in"))
      (node (ref "U32") (pin "2") (pinfunction "VSS_2") (pintype "power_in"))
      (node (ref "U33") (pin "8") (pinfunction "VSS_8") (pintype "power_in"))
      (node (ref "U7") (pin "2") (pinfunction "VSS_2") (pintype "power_in"))
      (node (ref "U9") (pin "8") (pinfunction "VSS_8") (pintype "power_in"))
    )
    (net (code "3") (name "/AI1") (class "Default")
      (node (ref "R89") (pin "1") (pinfunction "1_1") (pintype "passive"))
      (node (ref "SV3") (pin "2") (pinfunction "2_2") (pintype "passive"))
    )
    (net (code "4") (name "/AI1G") (class "Default")
      (node (ref "R90") (pin "1") (pinfunction "1_1") (pintype "passive"))
      (node (ref "SV3") (pin "1") (pinfunction "1_1") (pintype "passive"))
    )
    (net (code "5") (name "/AI2") (class "Default")
      (node (ref "R70") (pin "1") (pinfunction "1_1") (pintype "passive"))
      (node (ref "SV3") (pin "4") (pinfunction "4_4") (pintype "passive"))
    )
    (net (code "6") (name "/AI2G") (class "Default")
      (node (ref "R71") (pin "1") (pinfunction "1_1") (pintype "passive"))
      (node (ref "SV3") (pin "3") (pinfunction "3_3") (pintype "passive"))
    )
    (net (code "7") (name "/AI3") (class "Default")
      (node (ref "R41") (pin "1") (pinfunction "1_1") (pintype "passive"))
      (node (ref "SV3") (pin "6") (pinfunction "6_6") (pintype "passive"))
    )
    (net (code "8") (name "/AI3G") (class "Default")
      (node (ref "R47") (pin "1") (pinfunction "1_1") (pintype "passive"))
      (node (ref "SV3") (pin "5") (pinfunction "5_5") (pintype "passive"))
    )
    (net (code "9") (name "/AI4") (class "Default")
      (node (ref "R15") (pin "1") (pinfunction "1_1") (pintype "passive"))
      (node (ref "SV3") (pin "8") (pinfunction "8_8") (pintype "passive"))
    )
    (net (code "10") (name "/AI4G") (class "Default")
      (node (ref "R19") (pin "1") (pinfunction "1_1") (pintype "passive"))
      (node (ref "SV3") (pin "7") (pinfunction "7_7") (pintype "passive"))
    )
    (net (code "11") (name "/AIN") (class "Default")
      (node (ref "R21") (pin "1") (pinfunction "1_1") (pintype "passive"))
      (node (ref "U7") (pin "1") (pinfunction "VOUT_1") (pintype "output"))
      (node (ref "U9") (pin "3") (pinfunction "RA4_3") (pintype "bidirectional"))
    )
    (net (code "12") (name "/AIN_A1") (class "Default")
      (node (ref "R49") (pin "1") (pinfunction "1_1") (pintype "passive"))
      (node (ref "U20") (pin "1") (pinfunction "VOUT_1") (pintype "output"))
      (node (ref "U21") (pin "3") (pinfunction "RA4_3") (pintype "bidirectional"))
    )
    (net (code "13") (name "/AIN_A2") (class "Default")
      (node (ref "R78") (pin "1") (pinfunction "1_1") (pintype "passive"))
      (node (ref "U26") (pin "1") (pinfunction "VOUT_1") (pintype "output"))
      (node (ref "U27") (pin "3") (pinfunction "RA4_3") (pintype "bidirectional"))
    )
    (net (code "14") (name "/AIN_A3") (class "Default")
      (node (ref "R92") (pin "1") (pinfunction "1_1") (pintype "passive"))
      (node (ref "U32") (pin "1") (pinfunction "VOUT_1") (pintype "output"))
      (node (ref "U33") (pin "3") (pinfunction "RA4_3") (pintype "bidirectional"))
    )
    (net (code "15") (name "/DI1") (class "Default")
      (node (ref "B8") (pin "AC1") (pinfunction "AC1_AC1") (pintype "passive"))
      (node (ref "SV1") (pin "8") (pinfunction "8_8") (pintype "passive"))
    )
    (net (code "16") (name "/DI1G") (class "Default")
      (node (ref "B8") (pin "AC2") (pinfunction "AC2_AC2") (pintype "passive"))
      (node (ref "SV1") (pin "7") (pinfunction "7_7") (pintype "passive"))
    )
    (net (code "17") (name "/DI2") (class "Default")
      (node (ref "B6") (pin "AC1") (pinfunction "AC1_AC1") (pintype "passive"))
      (node (ref "SV1") (pin "6") (pinfunction "6_6") (pintype "passive"))
    )
    (net (code "18") (name "/DI2G") (class "Default")
      (node (ref "B6") (pin "AC2") (pinfunction "AC2_AC2") (pintype "passive"))
      (node (ref "SV1") (pin "5") (pinfunction "5_5") (pintype "passive"))
    )
    (net (code "19") (name "/DI3") (class "Default")
      (node (ref "B4") (pin "AC1") (pinfunction "AC1_AC1") (pintype "passive"))
      (node (ref "SV1") (pin "4") (pinfunction "4_4") (pintype "passive"))
    )
    (net (code "20") (name "/DI3G") (class "Default")
      (node (ref "B4") (pin "AC2") (pinfunction "AC2_AC2") (pintype "passive"))
      (node (ref "SV1") (pin "3") (pinfunction "3_3") (pintype "passive"))
    )
    (net (code "21") (name "/DI4") (class "Default")
      (node (ref "B2") (pin "AC1") (pinfunction "AC1_AC1") (pintype "passive"))
      (node (ref "SV1") (pin "2") (pinfunction "2_2") (pintype "passive"))
    )
    (net (code "22") (name "/DI4G") (class "Default")
      (node (ref "B2") (pin "AC2") (pinfunction "AC2_AC2") (pintype "passive"))
      (node (ref "SV1") (pin "1") (pinfunction "1_1") (pintype "passive"))
    )
    (net (code "23") (name "/DO1") (class "Default")
      (node (ref "R45") (pin "2") (pinfunction "2_2") (pintype "passive"))
      (node (ref "R46") (pin "1") (pinfunction "1_1") (pintype "passive"))
      (node (ref "SV2") (pin "2") (pinfunction "2_2") (pintype "passive"))
      (node (ref "U12") (pin "4") (pinfunction "S1_4") (pintype "passive"))
    )
    (net (code "24") (name "/DO1G") (class "Default")
      (node (ref "C12") (pin "2") (pinfunction "2_2") (pintype "passive"))
      (node (ref "R46") (pin "2") (pinfunction "2_2") (pintype "passive"))
      (node (ref "SV2") (pin "1") (pinfunction "1_1") (pintype "passive"))
      (node (ref "U12") (pin "3") (pinfunction "S2_3") (pintype "passive"))
    )
    (net (code "25") (name "/DO2") (class "Default")
      (node (ref "R55") (pin "2") (pinfunction "2_2") (pintype "passive"))
      (node (ref "R56") (pin "1") (pinfunction "1_1") (pintype "passive"))
      (node (ref "SV2") (pin "4") (pinfunction "4_4") (pintype "passive"))
      (node (ref "U14") (pin "4") (pinfunction "S1_4") (pintype "passive"))
    )
    (net (code "26") (name "/DO2G") (class "Default")
      (node (ref "C14") (pin "2") (pinfunction "2_2") (pintype "passive"))
      (node (ref "R56") (pin "2") (pinfunction "2_2") (pintype "passive"))
      (node (ref "SV2") (pin "3") (pinfunction "3_3") (pintype "passive"))
      (node (ref "U14") (pin "3") (pinfunction "S2_3") (pintype "passive"))
    )
    (net (code "27") (name "/DO3") (class "Default")
      (node (ref "R65") (pin "2") (pinfunction "2_2") (pintype "passive"))
      (node (ref "R66") (pin "1") (pinfunction "1_1") (pintype "passive"))
      (node (ref "SV2") (pin "6") (pinfunction "6_6") (pintype "passive"))
      (node (ref "U16") (pin "4") (pinfunction "S1_4") (pintype "passive"))
    )
    (net (code "28") (name "/DO3G") (class "Default")
      (node (ref "C16") (pin "2") (pinfunction "2_2") (pintype "passive"))
      (node (ref "R66") (pin "2") (pinfunction "2_2") (pintype "passive"))
      (node (ref "SV2") (pin "5") (pinfunction "5_5") (pintype "passive"))
      (node (ref "U16") (pin "3") (pinfunction "S2_3") (pintype "passive"))
    )
    (net (code "29") (name "/DO4") (class "Default")
      (node (ref "R75") (pin "2") (pinfunction "2_2") (pintype "passive"))
      (node (ref "R76") (pin "1") (pinfunction "1_1") (pintype "passive"))
      (node (ref "SV2") (pin "8") (pinfunction "8_8") (pintype "passive"))
      (node (ref "U18") (pin "4") (pinfunction "S1_4") (pintype "passive"))
    )
    (net (code "30") (name "/DO4G") (class "Default")
      (node (ref "C18") (pin "2") (pinfunction "2_2") (pintype "passive"))
      (node (ref "R76") (pin "2") (pinfunction "2_2") (pintype "passive"))
      (node (ref "SV2") (pin "7") (pinfunction "7_7") (pintype "passive"))
      (node (ref "U18") (pin "3") (pinfunction "S2_3") (pintype "passive"))
    )
    (net (code "31") (name "/DTR") (class "Default")
      (node (ref "JP6") (pin "1") (pinfunction "1_1") (pintype "passive"))
      (node (ref "Q3") (pin "2") (pinfunction "E_2") (pintype "passive"))
      (node (ref "R12") (pin "1") (pinfunction "1_1") (pintype "passive"))
    )
    (net (code "32") (name "/EN") (class "Default")
      (node (ref "C1") (pin "1") (pinfunction "1_1") (pintype "passive"))
      (node (ref "JP4") (pin "14") (pinfunction "14_14") (pintype "passive"))
      (node (ref "Q4") (pin "3") (pinfunction "C_3") (pintype "passive"))
      (node (ref "R3") (pin "1") (pinfunction "1_1") (pintype "passive"))
      (node (ref "RST1") (pin "2") (pinfunction "2_2") (pintype "passive"))
      (node (ref "U1") (pin "3") (pinfunction "EN_3") (pintype "bidirectional"))
    )
    (net (code "33") (name "/ICSPCLK") (class "Default")
      (node (ref "CLK1") (pin "TP") (pinfunction "PP_TP") (pintype "input"))
      (node (ref "U9") (pin "6") (pinfunction "RA1_6") (pintype "bidirectional"))
    )
    (net (code "34") (name "/ICSPCLK_A1") (class "Default")
      (node (ref "CLK3") (pin "TP") (pinfunction "PP_TP") (pintype "input"))
      (node (ref "U21") (pin "6") (pinfunction "RA1_6") (pintype "bidirectional"))
    )
    (net (code "35") (name "/ICSPCLK_A2") (class "Default")
      (node (ref "CLK5") (pin "TP") (pinfunction "PP_TP") (pintype "input"))
      (node (ref "U27") (pin "6") (pinfunction "RA1_6") (pintype "bidirectional"))
    )
    (net (code "36") (name "/ICSPCLK_A3") (class "Default")
      (node (ref "CLK7") (pin "TP") (pinfunction "PP_TP") (pintype "input"))
      (node (ref "U33") (pin "6") (pinfunction "RA1_6") (pintype "bidirectional"))
    )
    (net (code "37") (name "/ICSPDAT") (class "Default")
      (node (ref "DAT1") (pin "TP") (pinfunction "PP_TP") (pintype "input"))
      (node (ref "SJ2") (pin "2") (pinfunction "2_2") (pintype "passive"))
      (node (ref "U9") (pin "7") (pinfunction "RA0_7") (pintype "bidirectional"))
    )
    (net (code "38") (name "/ICSPDAT_A1") (class "Default")
      (node (ref "DAT3") (pin "TP") (pinfunction "PP_TP") (pintype "input"))
      (node (ref "SJ4") (pin "2") (pinfunction "2_2") (pintype "passive"))
      (node (ref "U21") (pin "7") (pinfunction "RA0_7") (pintype "bidirectional"))
    )
    (net (code "39") (name "/ICSPDAT_A2") (class "Default")
      (node (ref "DAT5") (pin "TP") (pinfunction "PP_TP") (pintype "input"))
      (node (ref "SJ6") (pin "2") (pinfunction "2_2") (pintype "passive"))
      (node (ref "U27") (pin "7") (pinfunction "RA0_7") (pintype "bidirectional"))
    )
    (net (code "40") (name "/ICSPDAT_A3") (class "Default")
      (node (ref "DAT7") (pin "TP") (pinfunction "PP_TP") (pintype "input"))
      (node (ref "SJ8") (pin "2") (pinfunction "2_2") (pintype "passive"))
      (node (ref "U33") (pin "7") (pinfunction "RA0_7") (pintype "bidirectional"))
    )
    (net (code "41") (name "/IO0") (class "Default")
      (node (ref "JP5") (pin "3") (pinfunction "3_3") (pintype "passive"))
      (node (ref "PGM1") (pin "2") (pinfunction "2_2") (pintype "passive"))
      (node (ref "Q3") (pin "3") (pinfunction "C_3") (pintype "passive"))
      (node (ref "R8") (pin "1") (pinfunction "1_1") (pintype "passive"))
      (node (ref "U1") (pin "25") (pinfunction "IO0_25") (pintype "bidirectional"))
    )
    (net (code "42") (name "/IO2") (class "Default")
      (node (ref "JP5") (pin "2") (pinfunction "2_2") (pintype "passive"))
      (node (ref "R9") (pin "2") (pinfunction "2_2") (pintype "passive"))
      (node (ref "U1") (pin "24") (pinfunction "IO2_24") (pintype "bidirectional"))
    )
    (net (code "43") (name "/IO4") (class "Default")
      (node (ref "JP5") (pin "4") (pinfunction "4_4") (pintype "passive"))
      (node (ref "U1") (pin "26") (pinfunction "IO4_26") (pintype "bidirectional"))
    )
    (net (code "44") (name "/IO5") (class "Default")
      (node (ref "JP5") (pin "7") (pinfunction "7_7") (pintype "passive"))
      (node (ref "U1") (pin "29") (pinfunction "IO5_29") (pintype "bidirectional"))
    )
    (net (code "45") (name "/IO6") (class "Default")
      (node (ref "U1") (pin "20") (pinfunction "CLK_20") (pintype "bidirectional"))
    )
    (net (code "46") (name "/IO7") (class "Default")
      (node (ref "U1") (pin "21") (pinfunction "SDO_21") (pintype "bidirectional"))
    )
    (net (code "47") (name "/IO8") (class "Default")
      (node (ref "U1") (pin "22") (pinfunction "SD1_22") (pintype "bidirectional"))
    )
    (net (code "48") (name "/IO9") (class "Default")
      (node (ref "U1") (pin "17") (pinfunction "SD2_17") (pintype "bidirectional"))
    )
    (net (code "49") (name "/IO10") (class "Default")
      (node (ref "U1") (pin "18") (pinfunction "SD3_18") (pintype "bidirectional"))
    )
    (net (code "50") (name "/IO11") (class "Default")
      (node (ref "U1") (pin "19") (pinfunction "CMD_19") (pintype "bidirectional"))
    )
    (net (code "51") (name "/IO12") (class "Default")
      (node (ref "JP4") (pin "3") (pinfunction "3_3") (pintype "passive"))
      (node (ref "S1") (pin "1") (pinfunction "S_1") (pintype "passive"))
      (node (ref "U1") (pin "14") (pinfunction "IO12_14") (pintype "bidirectional"))
    )
    (net (code "52") (name "/IO13") (class "Default")
      (node (ref "JP4") (pin "2") (pinfunction "2_2") (pintype "passive"))
      (node (ref "LED2") (pin "A") (pinfunction "A_A") (pintype "passive"))
      (node (ref "U1") (pin "16") (pinfunction "IO13_16") (pintype "bidirectional"))
    )
    (net (code "53") (name "/IO14") (class "Default")
      (node (ref "C11") (pin "1") (pinfunction "1_1") (pintype "passive"))
      (node (ref "JP4") (pin "4") (pinfunction "4_4") (pintype "passive"))
      (node (ref "L2") (pin "2") (pinfunction "2_2") (pintype "passive"))
      (node (ref "U1") (pin "13") (pinfunction "IO14_13") (pintype "bidirectional"))
    )
    (net (code "54") (name "/IO15") (class "Default")
      (node (ref "JP5") (pin "1") (pinfunction "1_1") (pintype "passive"))
      (node (ref "U1") (pin "23") (pinfunction "IO15_23") (pintype "bidirectional"))
    )
    (net (code "55") (name "/IO16") (class "Default")
      (node (ref "JP5") (pin "5") (pinfunction "5_5") (pintype "passive"))
      (node (ref "U1") (pin "27") (pinfunction "IO16_27") (pintype "bidirectional"))
    )
    (net (code "56") (name "/IO17") (class "Default")
      (node (ref "JP5") (pin "6") (pinfunction "6_6") (pintype "passive"))
      (node (ref "U1") (pin "28") (pinfunction "IO17_28") (pintype "bidirectional"))
    )
    (net (code "57") (name "/IO18") (class "Default")
      (node (ref "JP5") (pin "8") (pinfunction "8_8") (pintype "passive"))
      (node (ref "U1") (pin "30") (pinfunction "IO18_30") (pintype "bidirectional"))
    )
    (net (code "58") (name "/IO19") (class "Default")
      (node (ref "JP5") (pin "9") (pinfunction "9_9") (pintype "passive"))
      (node (ref "U1") (pin "31") (pinfunction "IO19_31") (pintype "bidirectional"))
    )
    (net (code "59") (name "/IO21") (class "Default")
      (node (ref "JP5") (pin "10") (pinfunction "10_10") (pintype "passive"))
      (node (ref "U1") (pin "33") (pinfunction "IO21_33") (pintype "bidirectional"))
    )
    (net (code "60") (name "/IO22") (class "Default")
      (node (ref "C29") (pin "1") (pinfunction "1_1") (pintype "passive"))
      (node (ref "JP5") (pin "13") (pinfunction "13_13") (pintype "passive"))
      (node (ref "L6") (pin "2") (pinfunction "2_2") (pintype "passive"))
      (node (ref "U1") (pin "36") (pinfunction "IO22_36") (pintype "bidirectional"))
    )
    (net (code "61") (name "/IO23") (class "Default")
      (node (ref "C35") (pin "1") (pinfunction "1_1") (pintype "passive"))
      (node (ref "JP5") (pin "14") (pinfunction "14_14") (pintype "passive"))
      (node (ref "L8") (pin "2") (pinfunction "2_2") (pintype "passive"))
      (node (ref "U1") (pin "37") (pinfunction "IO23_37") (pintype "bidirectional"))
    )
    (net (code "62") (name "/IO25") (class "Default")
      (node (ref "JP4") (pin "7") (pinfunction "7_7") (pintype "passive"))
      (node (ref "R63") (pin "1") (pinfunction "1_1") (pintype "passive"))
      (node (ref "U1") (pin "10") (pinfunction "IO25_10") (pintype "bidirectional"))
    )
    (net (code "63") (name "/IO26") (class "Default")
      (node (ref "JP4") (pin "6") (pinfunction "6_6") (pintype "passive"))
      (node (ref "R73") (pin "1") (pinfunction "1_1") (pintype "passive"))
      (node (ref "U1") (pin "11") (pinfunction "IO26_11") (pintype "bidirectional"))
    )
    (net (code "64") (name "/IO27") (class "Default")
      (node (ref "C23") (pin "1") (pinfunction "1_1") (pintype "passive"))
      (node (ref "JP4") (pin "5") (pinfunction "5_5") (pintype "passive"))
      (node (ref "L4") (pin "2") (pinfunction "2_2") (pintype "passive"))
      (node (ref "U1") (pin "12") (pinfunction "IO27_12") (pintype "bidirectional"))
    )
    (net (code "65") (name "/IO32") (class "Default")
      (node (ref "JP4") (pin "9") (pinfunction "9_9") (pintype "passive"))
      (node (ref "R43") (pin "1") (pinfunction "1_1") (pintype "passive"))
      (node (ref "U1") (pin "8") (pinfunction "IO32_8") (pintype "bidirectional"))
    )
    (net (code "66") (name "/IO33") (class "Default")
      (node (ref "JP4") (pin "8") (pinfunction "8_8") (pintype "passive"))
      (node (ref "R53") (pin "1") (pinfunction "1_1") (pintype "passive"))
      (node (ref "U1") (pin "9") (pinfunction "IO33_9") (pintype "bidirectional"))
    )
    (net (code "67") (name "/IO34") (class "Default")
      (node (ref "JP4") (pin "11") (pinfunction "11_11") (pintype "passive"))
      (node (ref "R30") (pin "1") (pinfunction "1_1") (pintype "passive"))
      (node (ref "U1") (pin "6") (pinfunction "IO34_6") (pintype "bidirectional"))
      (node (ref "U8") (pin "4") (pinfunction "COLLECTOR_4") (pintype "bidirectional"))
    )
    (net (code "68") (name "/IO35") (class "Default")
      (node (ref "JP4") (pin "10") (pinfunction "10_10") (pintype "passive"))
      (node (ref "R36") (pin "1") (pinfunction "1_1") (pintype "passive"))
      (node (ref "U1") (pin "7") (pinfunction "IO35_7") (pintype "bidirectional"))
      (node (ref "U10") (pin "4") (pinfunction "COLLECTOR_4") (pintype "bidirectional"))
    )
    (net (code "69") (name "/IO36") (class "Default")
      (node (ref "JP4") (pin "13") (pinfunction "13_13") (pintype "passive"))
      (node (ref "R18") (pin "1") (pinfunction "1_1") (pintype "passive"))
      (node (ref "U1") (pin "4") (pinfunction "SENSOR_VP_4") (pintype "bidirectional"))
      (node (ref "U4") (pin "4") (pinfunction "COLLECTOR_4") (pintype "bidirectional"))
    )
    (net (code "70") (name "/IO39") (class "Default")
      (node (ref "JP4") (pin "12") (pinfunction "12_12") (pintype "passive"))
      (node (ref "R24") (pin "1") (pinfunction "1_1") (pintype "passive"))
      (node (ref "U1") (pin "5") (pinfunction "SENSOR_VN_5") (pintype "bidirectional"))
      (node (ref "U6") (pin "4") (pinfunction "COLLECTOR_4") (pintype "bidirectional"))
    )
    (net (code "71") (name "/LED") (class "Default")
      (node (ref "U11") (pin "2") (pinfunction "CATHODE_2") (pintype "bidirectional"))
      (node (ref "U9") (pin "5") (pinfunction "RA2_5") (pintype "bidirectional"))
    )
    (net (code "72") (name "/LED_A1") (class "Default")
      (node (ref "U21") (pin "5") (pinfunction "RA2_5") (pintype "bidirectional"))
      (node (ref "U22") (pin "2") (pinfunction "CATHODE_2") (pintype "bidirectional"))
    )
    (net (code "73") (name "/LED_A2") (class "Default")
      (node (ref "U27") (pin "5") (pinfunction "RA2_5") (pintype "bidirectional"))
      (node (ref "U28") (pin "2") (pinfunction "CATHODE_2") (pintype "bidirectional"))
    )
    (net (code "74") (name "/LED_A3") (class "Default")
      (node (ref "U33") (pin "5") (pinfunction "RA2_5") (pintype "bidirectional"))
      (node (ref "U34") (pin "2") (pinfunction "CATHODE_2") (pintype "bidirectional"))
    )
    (net (code "75") (name "/MCLR") (class "Default")
      (node (ref "MCLR1") (pin "TP") (pinfunction "PP_TP") (pintype "input"))
      (node (ref "U9") (pin "4") (pinfunction "RA3_4") (pintype "bidirectional"))
    )
    (net (code "76") (name "/MCLR_A1") (class "Default")
      (node (ref "MCLR3") (pin "TP") (pinfunction "PP_TP") (pintype "input"))
      (node (ref "U21") (pin "4") (pinfunction "RA3_4") (pintype "bidirectional"))
    )
    (net (code "77") (name "/MCLR_A2") (class "Default")
      (node (ref "MCLR5") (pin "TP") (pinfunction "PP_TP") (pintype "input"))
      (node (ref "U27") (pin "4") (pinfunction "RA3_4") (pintype "bidirectional"))
    )
    (net (code "78") (name "/MCLR_A3") (class "Default")
      (node (ref "MCLR7") (pin "TP") (pinfunction "PP_TP") (pintype "input"))
      (node (ref "U33") (pin "4") (pinfunction "RA3_4") (pintype "bidirectional"))
    )
    (net (code "79") (name "/RTS") (class "Default")
      (node (ref "JP6") (pin "2") (pinfunction "2_2") (pintype "passive"))
      (node (ref "Q4") (pin "2") (pinfunction "E_2") (pintype "passive"))
      (node (ref "R11") (pin "1") (pinfunction "1_1") (pintype "passive"))
    )
    (net (code "80") (name "/RXD0") (class "Default")
      (node (ref "JP5") (pin "11") (pinfunction "11_11") (pintype "passive"))
      (node (ref "P2") (pin "1") (pinfunction "1_1") (pintype "passive"))
      (node (ref "U1") (pin "34") (pinfunction "RXD0_34") (pintype "bidirectional"))
    )
    (net (code "81") (name "/TXD0") (class "Default")
      (node (ref "JP5") (pin "12") (pinfunction "12_12") (pintype "passive"))
      (node (ref "P2") (pin "2") (pinfunction "2_2") (pintype "passive"))
      (node (ref "U1") (pin "35") (pinfunction "TXD0_35") (pintype "bidirectional"))
    )
    (net (code "82") (name "GND") (class "Default")
      (node (ref "C1") (pin "2") (pinfunction "2_2") (pintype "passive"))
      (node (ref "C11") (pin "2") (pinfunction "2_2") (pintype "passive"))
      (node (ref "C20") (pin "2") (pinfunction "2_2") (pintype "passive"))
      (node (ref "C21") (pin "2") (pinfunction "2_2") (pintype "passive"))
      (node (ref "C23") (pin "2") (pinfunction "2_2") (pintype "passive"))
      (node (ref "C29") (pin "2") (pinfunction "2_2") (pintype "passive"))
      (node (ref "C35") (pin "2") (pinfunction "2_2") (pintype "passive"))
      (node (ref "JP4") (pin "1") (pinfunction "1_1") (pintype "passive"))
      (node (ref "P2") (pin "3") (pinfunction "3_3") (pintype "passive"))
      (node (ref "PGM1") (pin "1") (pinfunction "1_1") (pintype "passive"))
      (node (ref "R1") (pin "1") (pinfunction "1_1") (pintype "passive"))
      (node (ref "R10") (pin "1") (pinfunction "1_1") (pintype "passive"))
      (node (ref "R26") (pin "1") (pinfunction "1_1") (pintype "passive"))
      (node (ref "R44") (pin "1") (pinfunction "1_1") (pintype "passive"))
      (node (ref "R51") (pin "1") (pinfunction "1_1") (pintype "passive"))
      (node (ref "R54") (pin "1") (pinfunction "1_1") (pintype "passive"))
      (node (ref "R64") (pin "1") (pinfunction "1_1") (pintype "passive"))
      (node (ref "R74") (pin "1") (pinfunction "1_1") (pintype "passive"))
      (node (ref "R80") (pin "1") (pinfunction "1_1") (pintype "passive"))
      (node (ref "R9") (pin "1") (pinfunction "1_1") (pintype "passive"))
      (node (ref "R94") (pin "1") (pinfunction "1_1") (pintype "passive"))
      (node (ref "RST1") (pin "1") (pinfunction "1_1") (pintype "passive"))
      (node (ref "T2") (pin "E") (pinfunction "E_E") (pintype "passive"))
      (node (ref "T4") (pin "E") (pinfunction "E_E") (pintype "passive"))
      (node (ref "T6") (pin "E") (pinfunction "E_E") (pintype "passive"))
      (node (ref "T8") (pin "E") (pinfunction "E_E") (pintype "passive"))
      (node (ref "U1") (pin "1") (pinfunction "GND_1") (pintype "bidirectional"))
      (node (ref "U1") (pin "15") (pinfunction "GND_15") (pintype "bidirectional"))
      (node (ref "U1") (pin "38") (pinfunction "GND_38") (pintype "bidirectional"))
      (node (ref "U1") (pin "GND") (pinfunction "GND_GND") (pintype "bidirectional"))
      (node (ref "U10") (pin "3") (pinfunction "EMITER_3") (pintype "bidirectional"))
      (node (ref "U17") (pin "3") (pinfunction "GND_3") (pintype "input"))
      (node (ref "U2") (pin "2") (pinfunction "-VIN_2") (pintype "input"))
      (node (ref "U4") (pin "3") (pinfunction "EMITER_3") (pintype "bidirectional"))
      (node (ref "U6") (pin "3") (pinfunction "EMITER_3") (pintype "bidirectional"))
      (node (ref "U8") (pin "3") (pinfunction "EMITER_3") (pintype "bidirectional"))
      (node (ref "X1") (pin "1") (pinfunction "S_1") (pintype "passive"))
    )
    (net (code "83") (name "Net-(B2-Pad+)") (class "Default")
      (node (ref "B2") (pin "+") (pinfunction "+_+") (pintype "passive"))
      (node (ref "D2") (pin "C") (pinfunction "C_C") (pintype "passive"))
      (node (ref "R16") (pin "1") (pinfunction "1_1") (pintype "passive"))
    )
    (net (code "84") (name "Net-(B4-Pad+)") (class "Default")
      (node (ref "B4") (pin "+") (pinfunction "+_+") (pintype "passive"))
      (node (ref "D4") (pin "C") (pinfunction "C_C") (pintype "passive"))
      (node (ref "R22") (pin "1") (pinfunction "1_1") (pintype "passive"))
    )
    (net (code "85") (name "Net-(B6-Pad+)") (class "Default")
      (node (ref "B6") (pin "+") (pinfunction "+_+") (pintype "passive"))
      (node (ref "D6") (pin "C") (pinfunction "C_C") (pintype "passive"))
      (node (ref "R28") (pin "1") (pinfunction "1_1") (pintype "passive"))
    )
    (net (code "86") (name "Net-(B8-Pad+)") (class "Default")
      (node (ref "B8") (pin "+") (pinfunction "+_+") (pintype "passive"))
      (node (ref "D8") (pin "C") (pinfunction "C_C") (pintype "passive"))
      (node (ref "R34") (pin "1") (pinfunction "1_1") (pintype "passive"))
    )
    (net (code "87") (name "Net-(C12-Pad1)") (class "Default")
      (node (ref "C12") (pin "1") (pinfunction "1_1") (pintype "passive"))
      (node (ref "R45") (pin "1") (pinfunction "1_1") (pintype "passive"))
    )
    (net (code "88") (name "Net-(C14-Pad1)") (class "Default")
      (node (ref "C14") (pin "1") (pinfunction "1_1") (pintype "passive"))
      (node (ref "R55") (pin "1") (pinfunction "1_1") (pintype "passive"))
    )
    (net (code "89") (name "Net-(C16-Pad1)") (class "Default")
      (node (ref "C16") (pin "1") (pinfunction "1_1") (pintype "passive"))
      (node (ref "R65") (pin "1") (pinfunction "1_1") (pintype "passive"))
    )
    (net (code "90") (name "Net-(C18-Pad1)") (class "Default")
      (node (ref "C18") (pin "1") (pinfunction "1_1") (pintype "passive"))
      (node (ref "R75") (pin "1") (pinfunction "1_1") (pintype "passive"))
    )
    (net (code "91") (name "Net-(L2-Pad1)") (class "Default")
      (node (ref "L2") (pin "1") (pinfunction "1_1") (pintype "passive"))
      (node (ref "R27") (pin "1") (pinfunction "1_1") (pintype "passive"))
    )
    (net (code "92") (name "Net-(L4-Pad1)") (class "Default")
      (node (ref "L4") (pin "1") (pinfunction "1_1") (pintype "passive"))
      (node (ref "R57") (pin "1") (pinfunction "1_1") (pintype "passive"))
    )
    (net (code "93") (name "Net-(L6-Pad1)") (class "Default")
      (node (ref "L6") (pin "1") (pinfunction "1_1") (pintype "passive"))
      (node (ref "R81") (pin "1") (pinfunction "1_1") (pintype "passive"))
    )
    (net (code "94") (name "Net-(L8-Pad1)") (class "Default")
      (node (ref "L8") (pin "1") (pinfunction "1_1") (pintype "passive"))
      (node (ref "R95") (pin "1") (pinfunction "1_1") (pintype "passive"))
    )
    (net (code "95") (name "Net-(LED2-PadC)") (class "Default")
      (node (ref "LED2") (pin "C") (pinfunction "C_C") (pintype "passive"))
      (node (ref "R10") (pin "2") (pinfunction "2_2") (pintype "passive"))
    )
    (net (code "96") (name "Net-(Q3-B)") (class "Default")
      (node (ref "Q3") (pin "1") (pinfunction "B_1") (pintype "passive"))
      (node (ref "R11") (pin "2") (pinfunction "2_2") (pintype "passive"))
    )
    (net (code "97") (name "Net-(Q4-B)") (class "Default")
      (node (ref "Q4") (pin "1") (pinfunction "B_1") (pintype "passive"))
      (node (ref "R12") (pin "2") (pinfunction "2_2") (pintype "passive"))
    )
    (net (code "98") (name "Net-(R20-Pad2)") (class "Default")
      (node (ref "R20") (pin "2") (pinfunction "2_2") (pintype "passive"))
      (node (ref "SJ2") (pin "1") (pinfunction "1_1") (pintype "passive"))
    )
    (net (code "99") (name "Net-(R43-Pad2)") (class "Default")
      (node (ref "R43") (pin "2") (pinfunction "2_2") (pintype "passive"))
      (node (ref "R44") (pin "2") (pinfunction "2_2") (pintype "passive"))
      (node (ref "T2") (pin "B") (pinfunction "B_B") (pintype "passive"))
    )
    (net (code "100") (name "Net-(R48-Pad2)") (class "Default")
      (node (ref "R48") (pin "2") (pinfunction "2_2") (pintype "passive"))
      (node (ref "SJ4") (pin "1") (pinfunction "1_1") (pintype "passive"))
    )
    (net (code "101") (name "Net-(R53-Pad2)") (class "Default")
      (node (ref "R53") (pin "2") (pinfunction "2_2") (pintype "passive"))
      (node (ref "R54") (pin "2") (pinfunction "2_2") (pintype "passive"))
      (node (ref "T4") (pin "B") (pinfunction "B_B") (pintype "passive"))
    )
    (net (code "102") (name "Net-(R63-Pad2)") (class "Default")
      (node (ref "R63") (pin "2") (pinfunction "2_2") (pintype "passive"))
      (node (ref "R64") (pin "2") (pinfunction "2_2") (pintype "passive"))
      (node (ref "T6") (pin "B") (pinfunction "B_B") (pintype "passive"))
    )
    (net (code "103") (name "Net-(R73-Pad2)") (class "Default")
      (node (ref "R73") (pin "2") (pinfunction "2_2") (pintype "passive"))
      (node (ref "R74") (pin "2") (pinfunction "2_2") (pintype "passive"))
      (node (ref "T8") (pin "B") (pinfunction "B_B") (pintype "passive"))
    )
    (net (code "104") (name "Net-(R77-Pad2)") (class "Default")
      (node (ref "R77") (pin "2") (pinfunction "2_2") (pintype "passive"))
      (node (ref "SJ6") (pin "1") (pinfunction "1_1") (pintype "passive"))
    )
    (net (code "105") (name "Net-(R91-Pad2)") (class "Default")
      (node (ref "R91") (pin "2") (pinfunction "2_2") (pintype "passive"))
      (node (ref "SJ8") (pin "1") (pinfunction "1_1") (pintype "passive"))
    )
    (net (code "106") (name "Net-(S1-S1)") (class "Default")
      (node (ref "R1") (pin "2") (pinfunction "2_2") (pintype "passive"))
      (node (ref "S1") (pin "2") (pinfunction "S1_2") (pintype "passive"))
    )
    (net (code "107") (name "Net-(U4-ANODE)") (class "Default")
      (node (ref "C3") (pin "1") (pinfunction "1_1") (pintype "passive"))
      (node (ref "R16") (pin "2") (pinfunction "2_2") (pintype "passive"))
      (node (ref "R17") (pin "2") (pinfunction "2_2") (pintype "passive"))
      (node (ref "U4") (pin "1") (pinfunction "ANODE_1") (pintype "bidirectional"))
    )
    (net (code "108") (name "Net-(U4-CATHODE)") (class "Default")
      (node (ref "B2") (pin "-") (pinfunction "-_-") (pintype "passive"))
      (node (ref "C3") (pin "2") (pinfunction "2_2") (pintype "passive"))
      (node (ref "D2") (pin "A") (pinfunction "A_A") (pintype "passive"))
      (node (ref "R17") (pin "1") (pinfunction "1_1") (pintype "passive"))
      (node (ref "U4") (pin "2") (pinfunction "CATHODE_2") (pintype "bidirectional"))
    )
    (net (code "109") (name "Net-(U6-ANODE)") (class "Default")
      (node (ref "C6") (pin "1") (pinfunction "1_1") (pintype "passive"))
      (node (ref "R22") (pin "2") (pinfunction "2_2") (pintype "passive"))
      (node (ref "R23") (pin "2") (pinfunction "2_2") (pintype "passive"))
      (node (ref "U6") (pin "1") (pinfunction "ANODE_1") (pintype "bidirectional"))
    )
    (net (code "110") (name "Net-(U6-CATHODE)") (class "Default")
      (node (ref "B4") (pin "-") (pinfunction "-_-") (pintype "passive"))
      (node (ref "C6") (pin "2") (pinfunction "2_2") (pintype "passive"))
      (node (ref "D4") (pin "A") (pinfunction "A_A") (pintype "passive"))
      (node (ref "R23") (pin "1") (pinfunction "1_1") (pintype "passive"))
      (node (ref "U6") (pin "2") (pinfunction "CATHODE_2") (pintype "bidirectional"))
    )
    (net (code "111") (name "Net-(U7-+)") (class "Default")
      (node (ref "R15") (pin "2") (pinfunction "2_2") (pintype "passive"))
      (node (ref "R20") (pin "1") (pinfunction "1_1") (pintype "passive"))
      (node (ref "U7") (pin "3") (pinfunction "+_3") (pintype "input"))
    )
    (net (code "112") (name "Net-(U7--)") (class "Default")
      (node (ref "R19") (pin "2") (pinfunction "2_2") (pintype "passive"))
      (node (ref "R21") (pin "2") (pinfunction "2_2") (pintype "passive"))
      (node (ref "U7") (pin "4") (pinfunction "-_4") (pintype "input"))
    )
    (net (code "113") (name "Net-(U8-ANODE)") (class "Default")
      (node (ref "C8") (pin "1") (pinfunction "1_1") (pintype "passive"))
      (node (ref "R28") (pin "2") (pinfunction "2_2") (pintype "passive"))
      (node (ref "R29") (pin "2") (pinfunction "2_2") (pintype "passive"))
      (node (ref "U8") (pin "1") (pinfunction "ANODE_1") (pintype "bidirectional"))
    )
    (net (code "114") (name "Net-(U8-CATHODE)") (class "Default")
      (node (ref "B6") (pin "-") (pinfunction "-_-") (pintype "passive"))
      (node (ref "C8") (pin "2") (pinfunction "2_2") (pintype "passive"))
      (node (ref "D6") (pin "A") (pinfunction "A_A") (pintype "passive"))
      (node (ref "R29") (pin "1") (pinfunction "1_1") (pintype "passive"))
      (node (ref "U8") (pin "2") (pinfunction "CATHODE_2") (pintype "bidirectional"))
    )
    (net (code "115") (name "Net-(U10-ANODE)") (class "Default")
      (node (ref "C10") (pin "1") (pinfunction "1_1") (pintype "passive"))
      (node (ref "R34") (pin "2") (pinfunction "2_2") (pintype "passive"))
      (node (ref "R35") (pin "2") (pinfunction "2_2") (pintype "passive"))
      (node (ref "U10") (pin "1") (pinfunction "ANODE_1") (pintype "bidirectional"))
    )
    (net (code "116") (name "Net-(U10-CATHODE)") (class "Default")
      (node (ref "B8") (pin "-") (pinfunction "-_-") (pintype "passive"))
      (node (ref "C10") (pin "2") (pinfunction "2_2") (pintype "passive"))
      (node (ref "D8") (pin "A") (pinfunction "A_A") (pintype "passive"))
      (node (ref "R35") (pin "1") (pinfunction "1_1") (pintype "passive"))
      (node (ref "U10") (pin "2") (pinfunction "CATHODE_2") (pintype "bidirectional"))
    )
    (net (code "117") (name "Net-(U11-ANODE)") (class "Default")
      (node (ref "R25") (pin "1") (pinfunction "1_1") (pintype "passive"))
      (node (ref "U11") (pin "1") (pinfunction "ANODE_1") (pintype "bidirectional"))
    )
    (net (code "118") (name "Net-(U11-EMITER)") (class "Default")
      (node (ref "R26") (pin "2") (pinfunction "2_2") (pintype "passive"))
      (node (ref "R27") (pin "2") (pinfunction "2_2") (pintype "passive"))
      (node (ref "U11") (pin "3") (pinfunction "EMITER_3") (pintype "bidirectional"))
    )
    (net (code "119") (name "Net-(U12-C)") (class "Default")
      (node (ref "R42") (pin "1") (pinfunction "1_1") (pintype "passive"))
      (node (ref "T2") (pin "C") (pinfunction "C_C") (pintype "passive"))
      (node (ref "U12") (pin "2") (pinfunction "C_2") (pintype "passive"))
    )
    (net (code "120") (name "Net-(U14-C)") (class "Default")
      (node (ref "R52") (pin "1") (pinfunction "1_1") (pintype "passive"))
      (node (ref "T4") (pin "C") (pinfunction "C_C") (pintype "passive"))
      (node (ref "U14") (pin "2") (pinfunction "C_2") (pintype "passive"))
    )
    (net (code "121") (name "Net-(U16-C)") (class "Default")
      (node (ref "R62") (pin "1") (pinfunction "1_1") (pintype "passive"))
      (node (ref "T6") (pin "C") (pinfunction "C_C") (pintype "passive"))
      (node (ref "U16") (pin "2") (pinfunction "C_2") (pintype "passive"))
    )
    (net (code "122") (name "Net-(U17-IN)") (class "Default")
      (node (ref "C20") (pin "1") (pinfunction "1_1") (pintype "passive"))
      (node (ref "D1") (pin "C") (pinfunction "C_C") (pintype "passive"))
      (node (ref "U17") (pin "1") (pinfunction "IN_1") (pintype "input"))
      (node (ref "U2") (pin "1") (pinfunction "+VIN_1") (pintype "input"))
    )
    (net (code "123") (name "Net-(U18-C)") (class "Default")
      (node (ref "R72") (pin "1") (pinfunction "1_1") (pintype "passive"))
      (node (ref "T8") (pin "C") (pinfunction "C_C") (pintype "passive"))
      (node (ref "U18") (pin "2") (pinfunction "C_2") (pintype "passive"))
    )
    (net (code "124") (name "Net-(U20-+)") (class "Default")
      (node (ref "R41") (pin "2") (pinfunction "2_2") (pintype "passive"))
      (node (ref "R48") (pin "1") (pinfunction "1_1") (pintype "passive"))
      (node (ref "U20") (pin "3") (pinfunction "+_3") (pintype "input"))
    )
    (net (code "125") (name "Net-(U20--)") (class "Default")
      (node (ref "R47") (pin "2") (pinfunction "2_2") (pintype "passive"))
      (node (ref "R49") (pin "2") (pinfunction "2_2") (pintype "passive"))
      (node (ref "U20") (pin "4") (pinfunction "-_4") (pintype "input"))
    )
    (net (code "126") (name "Net-(U22-ANODE)") (class "Default")
      (node (ref "R50") (pin "1") (pinfunction "1_1") (pintype "passive"))
      (node (ref "U22") (pin "1") (pinfunction "ANODE_1") (pintype "bidirectional"))
    )
    (net (code "127") (name "Net-(U22-EMITER)") (class "Default")
      (node (ref "R51") (pin "2") (pinfunction "2_2") (pintype "passive"))
      (node (ref "R57") (pin "2") (pinfunction "2_2") (pintype "passive"))
      (node (ref "U22") (pin "3") (pinfunction "EMITER_3") (pintype "bidirectional"))
    )
    (net (code "128") (name "Net-(U26-+)") (class "Default")
      (node (ref "R70") (pin "2") (pinfunction "2_2") (pintype "passive"))
      (node (ref "R77") (pin "1") (pinfunction "1_1") (pintype "passive"))
      (node (ref "U26") (pin "3") (pinfunction "+_3") (pintype "input"))
    )
    (net (code "129") (name "Net-(U26--)") (class "Default")
      (node (ref "R71") (pin "2") (pinfunction "2_2") (pintype "passive"))
      (node (ref "R78") (pin "2") (pinfunction "2_2") (pintype "passive"))
      (node (ref "U26") (pin "4") (pinfunction "-_4") (pintype "input"))
    )
    (net (code "130") (name "Net-(U28-ANODE)") (class "Default")
      (node (ref "R79") (pin "1") (pinfunction "1_1") (pintype "passive"))
      (node (ref "U28") (pin "1") (pinfunction "ANODE_1") (pintype "bidirectional"))
    )
    (net (code "131") (name "Net-(U28-EMITER)") (class "Default")
      (node (ref "R80") (pin "2") (pinfunction "2_2") (pintype "passive"))
      (node (ref "R81") (pin "2") (pinfunction "2_2") (pintype "passive"))
      (node (ref "U28") (pin "3") (pinfunction "EMITER_3") (pintype "bidirectional"))
    )
    (net (code "132") (name "Net-(U32-+)") (class "Default")
      (node (ref "R89") (pin "2") (pinfunction "2_2") (pintype "passive"))
      (node (ref "R91") (pin "1") (pinfunction "1_1") (pintype "passive"))
      (node (ref "U32") (pin "3") (pinfunction "+_3") (pintype "input"))
    )
    (net (code "133") (name "Net-(U32--)") (class "Default")
      (node (ref "R90") (pin "2") (pinfunction "2_2") (pintype "passive"))
      (node (ref "R92") (pin "2") (pinfunction "2_2") (pintype "passive"))
      (node (ref "U32") (pin "4") (pinfunction "-_4") (pintype "input"))
    )
    (net (code "134") (name "Net-(U34-ANODE)") (class "Default")
      (node (ref "R93") (pin "1") (pinfunction "1_1") (pintype "passive"))
      (node (ref "U34") (pin "1") (pinfunction "ANODE_1") (pintype "bidirectional"))
    )
    (net (code "135") (name "Net-(U34-EMITER)") (class "Default")
      (node (ref "R94") (pin "2") (pinfunction "2_2") (pintype "passive"))
      (node (ref "R95") (pin "2") (pinfunction "2_2") (pintype "passive"))
      (node (ref "U34") (pin "3") (pinfunction "EMITER_3") (pintype "bidirectional"))
    )
    (net (code "136") (name "Net-(X1B-S)") (class "Default")
      (node (ref "D1") (pin "A") (pinfunction "A_A") (pintype "passive"))
      (node (ref "X1") (pin "2") (pinfunction "S_2") (pintype "passive"))
    )
    (net (code "137") (name "VCC") (class "Default")
      (node (ref "C21") (pin "1") (pinfunction "1_1") (pintype "passive"))
      (node (ref "P2") (pin "4") (pinfunction "4_4") (pintype "passive"))
      (node (ref "R18") (pin "2") (pinfunction "2_2") (pintype "passive"))
      (node (ref "R24") (pin "2") (pinfunction "2_2") (pintype "passive"))
      (node (ref "R3") (pin "2") (pinfunction "2_2") (pintype "passive"))
      (node (ref "R30") (pin "2") (pinfunction "2_2") (pintype "passive"))
      (node (ref "R36") (pin "2") (pinfunction "2_2") (pintype "passive"))
      (node (ref "R42") (pin "2") (pinfunction "2_2") (pintype "passive"))
      (node (ref "R52") (pin "2") (pinfunction "2_2") (pintype "passive"))
      (node (ref "R62") (pin "2") (pinfunction "2_2") (pintype "passive"))
      (node (ref "R72") (pin "2") (pinfunction "2_2") (pintype "passive"))
      (node (ref "R8") (pin "2") (pinfunction "2_2") (pintype "passive"))
      (node (ref "S1") (pin "4") (pinfunction "P1_4") (pintype "passive"))
      (node (ref "U1") (pin "2") (pinfunction "3V3_2") (pintype "bidirectional"))
      (node (ref "U11") (pin "4") (pinfunction "COLLECTOR_4") (pintype "bidirectional"))
      (node (ref "U12") (pin "1") (pinfunction "A_1") (pintype "passive"))
      (node (ref "U14") (pin "1") (pinfunction "A_1") (pintype "passive"))
      (node (ref "U16") (pin "1") (pinfunction "A_1") (pintype "passive"))
      (node (ref "U17") (pin "2") (pinfunction "OUT_2") (pintype "passive"))
      (node (ref "U18") (pin "1") (pinfunction "A_1") (pintype "passive"))
      (node (ref "U22") (pin "4") (pinfunction "COLLECTOR_4") (pintype "bidirectional"))
      (node (ref "U28") (pin "4") (pinfunction "COLLECTOR_4") (pintype "bidirectional"))
      (node (ref "U34") (pin "4") (pinfunction "COLLECTOR_4") (pintype "bidirectional"))
    )
    (net (code "138") (name "unconnected-(S1-P-Pad3)") (class "Default")
      (node (ref "S1") (pin "3") (pinfunction "P_3") (pintype "passive"))
    )
    (net (code "139") (name "unconnected-(U1-NC-Pad32)") (class "Default")
      (node (ref "U1") (pin "32") (pinfunction "NC_32") (pintype "bidirectional"))
    )
    (net (code "140") (name "unconnected-(U9-RA5-Pad2)") (class "Default")
      (node (ref "U9") (pin "2") (pinfunction "RA5_2") (pintype "bidirectional"))
    )
    (net (code "141") (name "unconnected-(U21-RA5-Pad2)") (class "Default")
      (node (ref "U21") (pin "2") (pinfunction "RA5_2") (pintype "bidirectional"))
    )
    (net (code "142") (name "unconnected-(U27-RA5-Pad2)") (class "Default")
      (node (ref "U27") (pin "2") (pinfunction "RA5_2") (pintype "bidirectional"))
    )
    (net (code "143") (name "unconnected-(U33-RA5-Pad2)") (class "Default")
      (node (ref "U33") (pin "2") (pinfunction "RA5_2") (pintype "bidirectional"))
    )
  )
)
